# WM1302_915_USB_without_SX1262_SKY66420_v.net
KiCad netlist of a schematic drawn in EAGLE
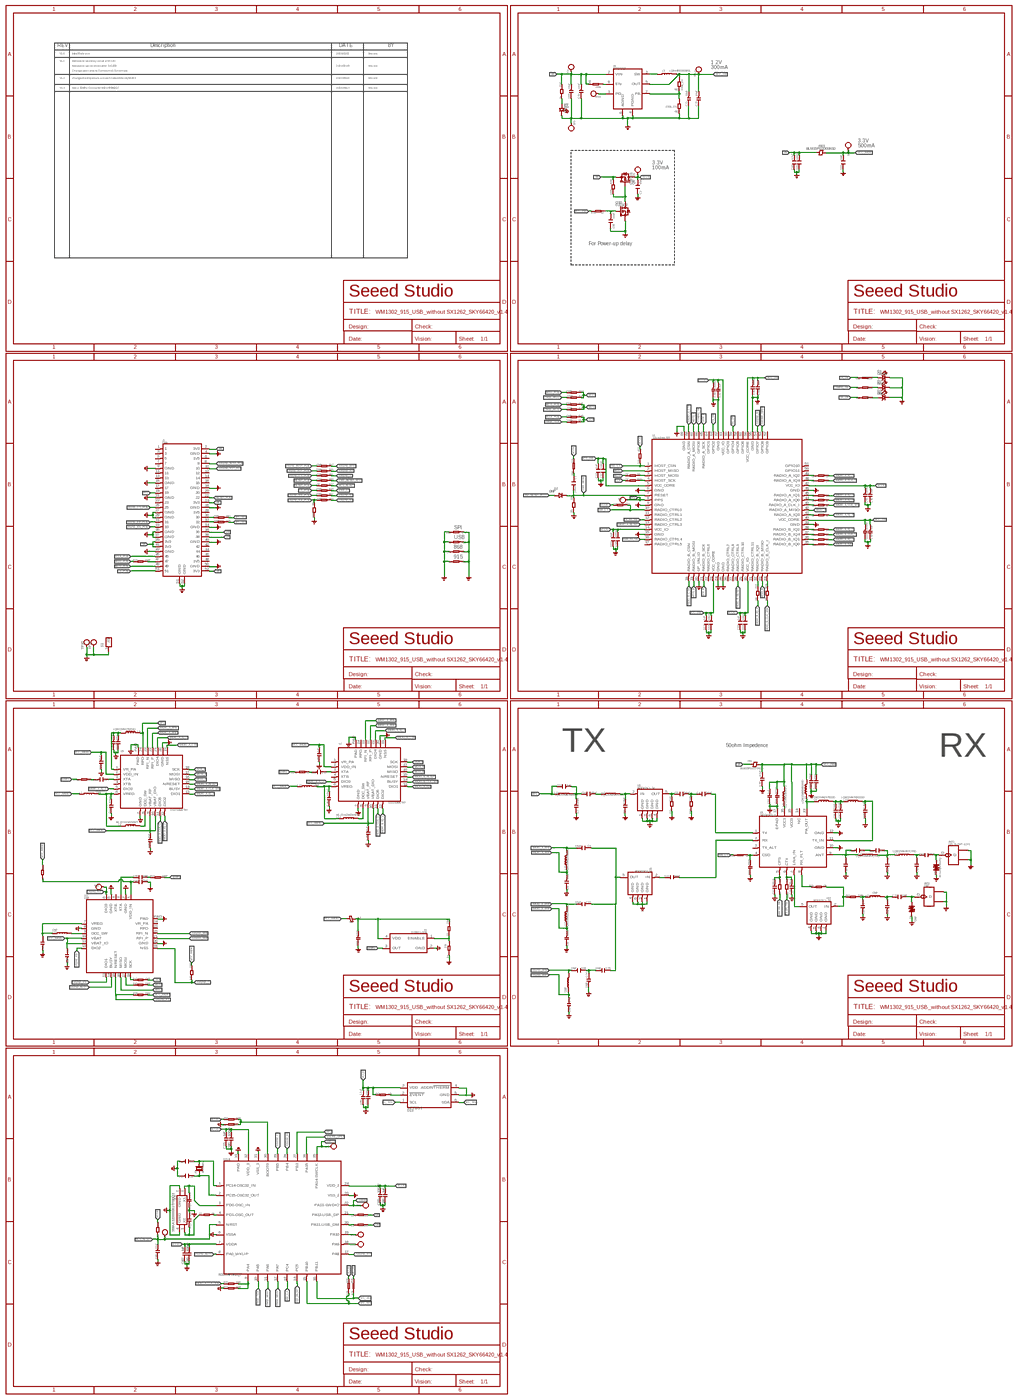
[diagram p0: schematic, sheet 1, overview]
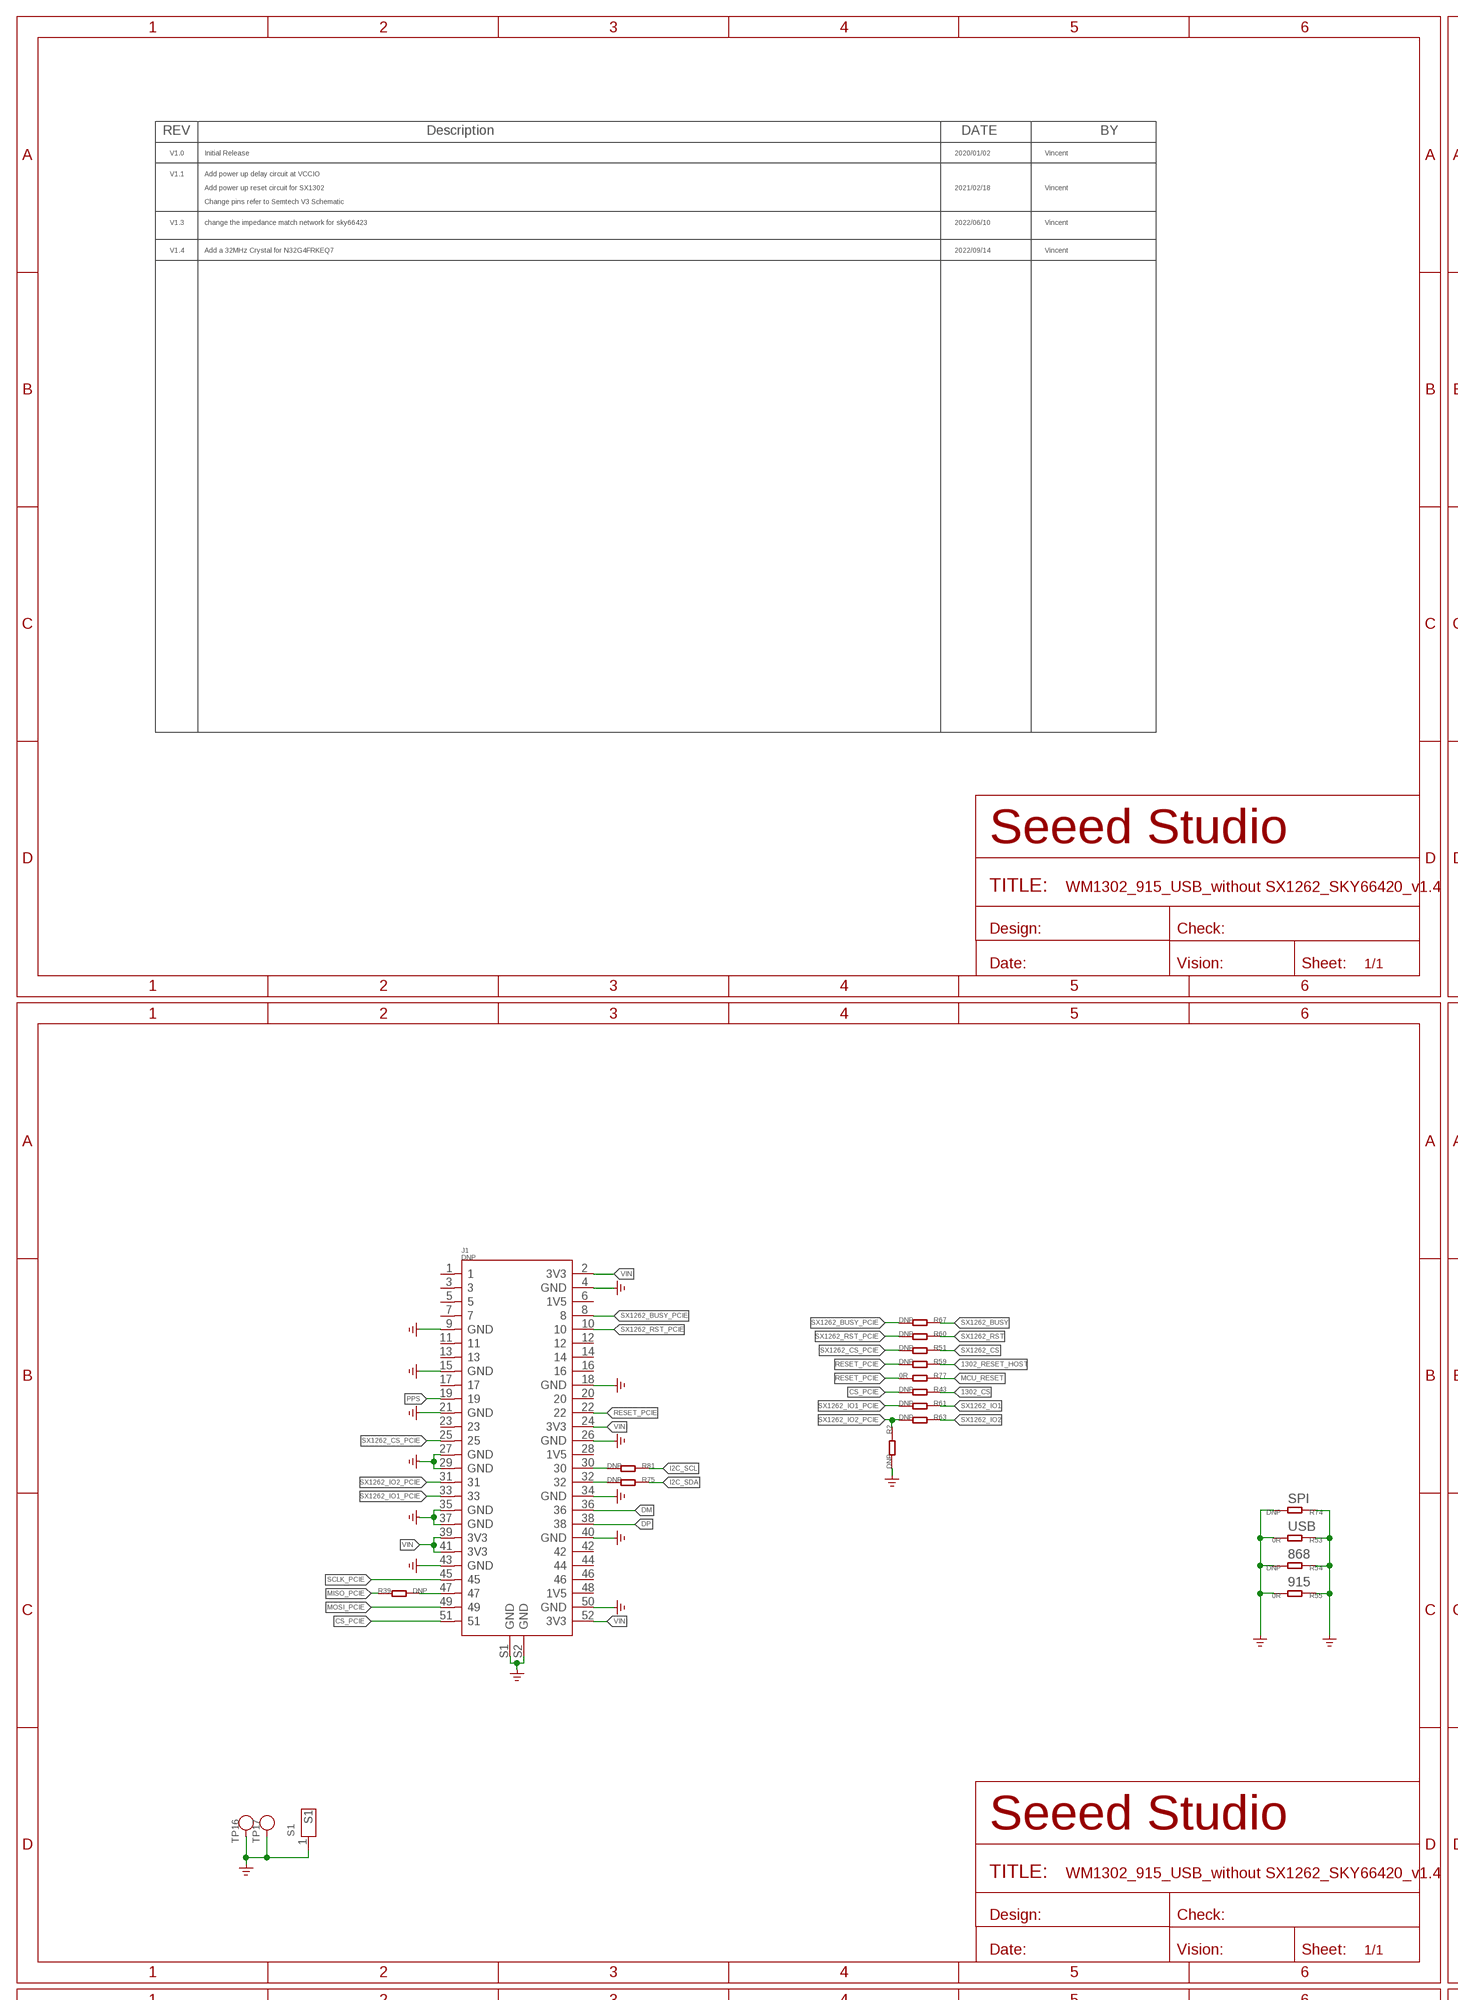
[diagram p1: schematic, sheet 1, part 1 of 4]
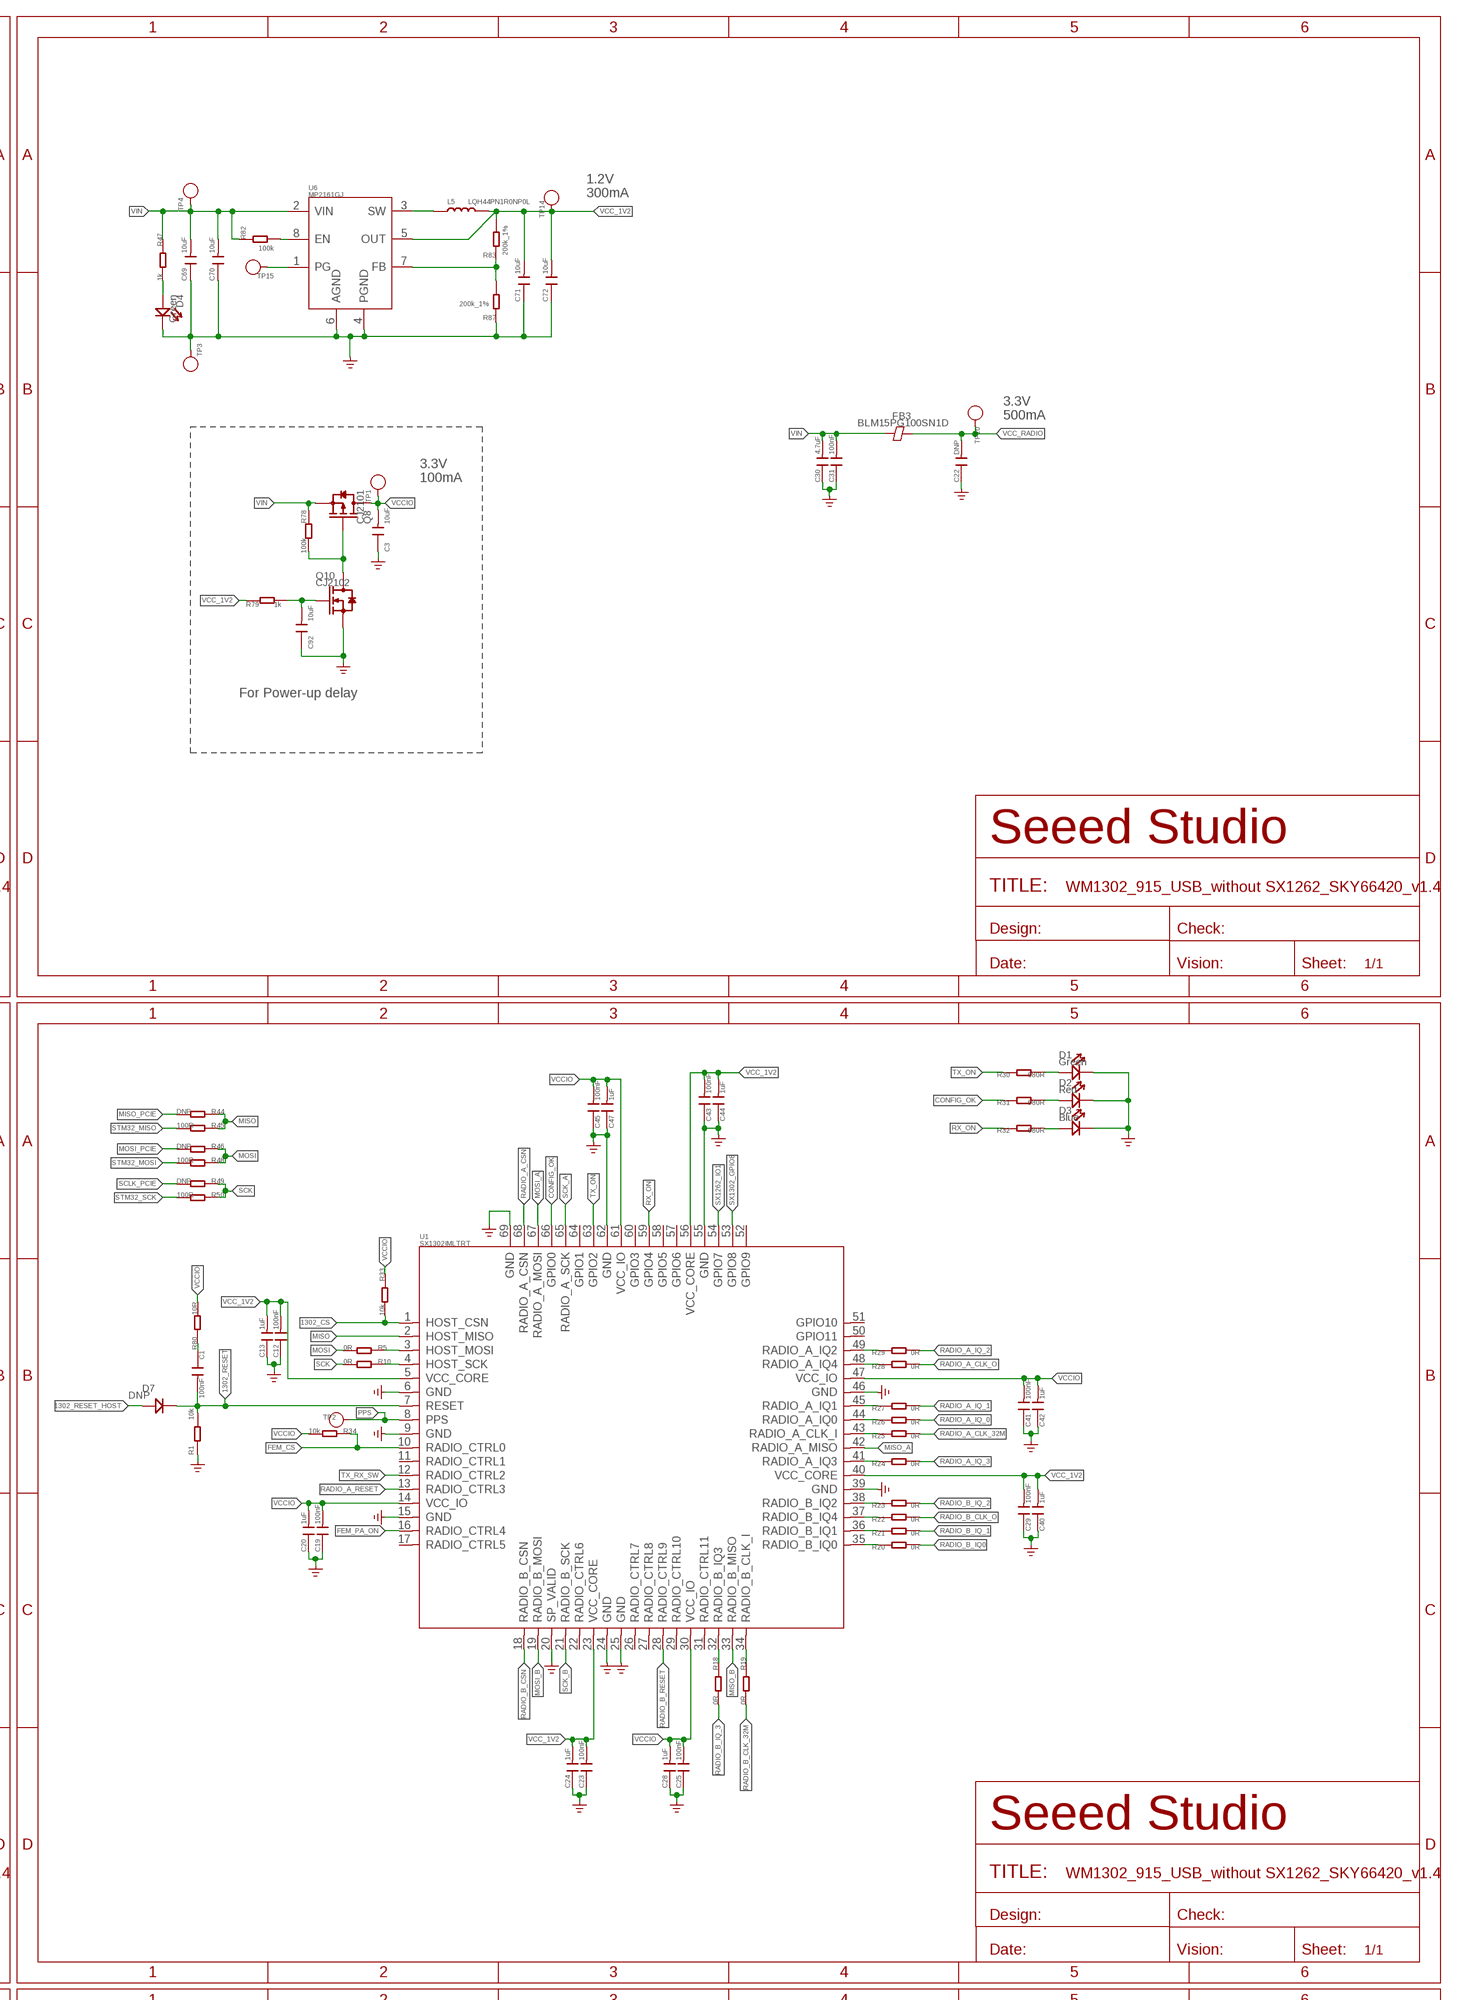
[diagram p2: schematic, sheet 1, part 2 of 4]
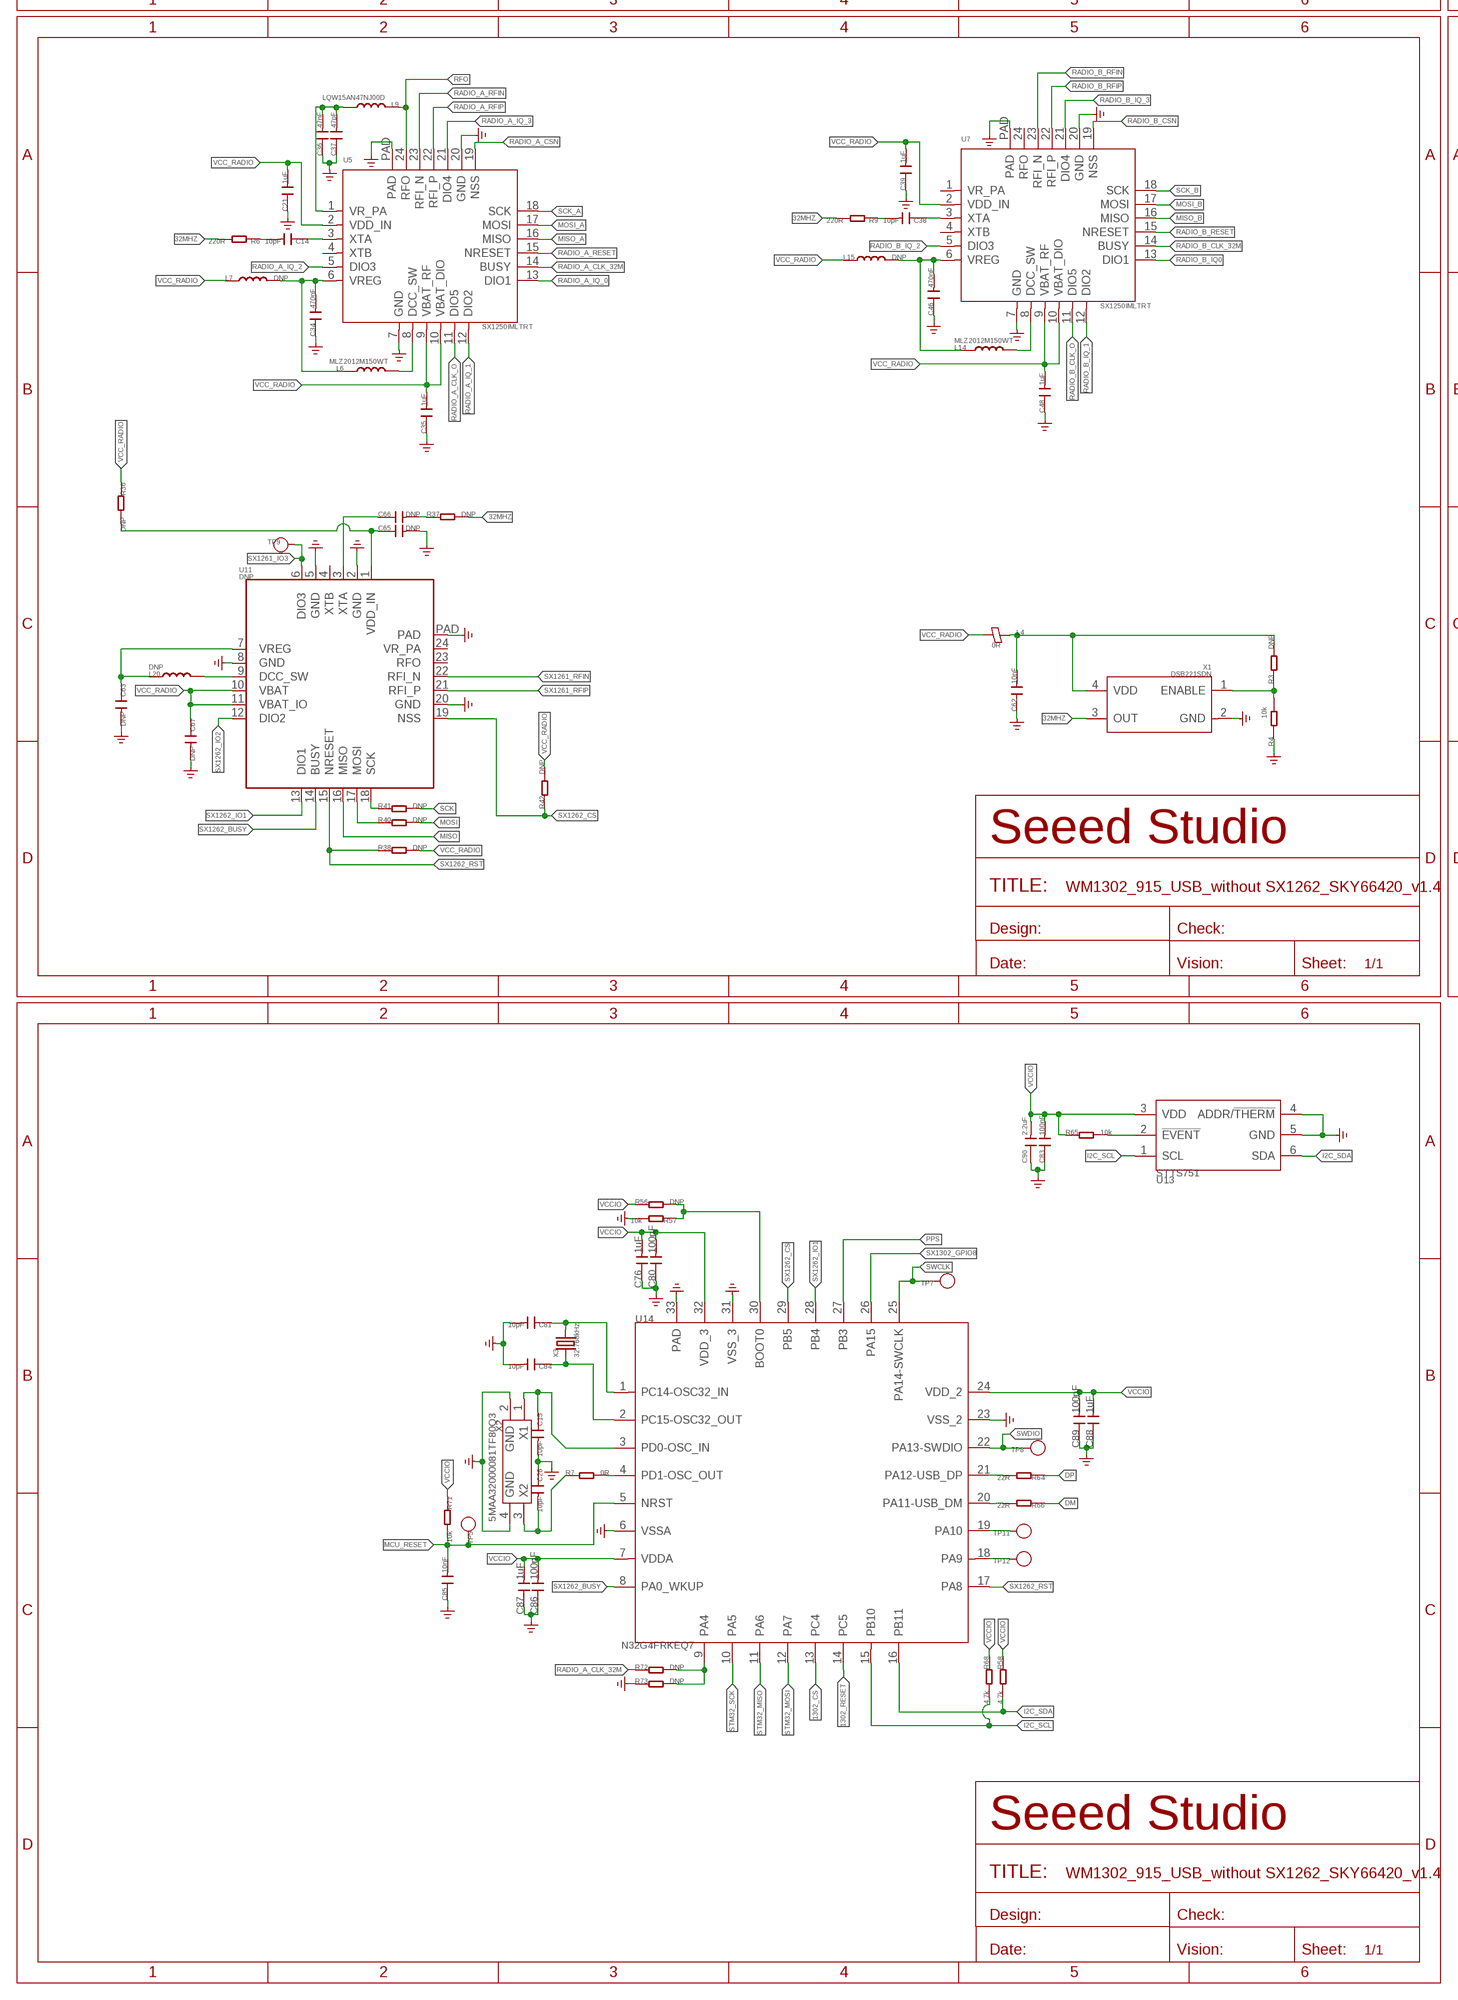
[diagram p3: schematic, sheet 1, part 3 of 4]
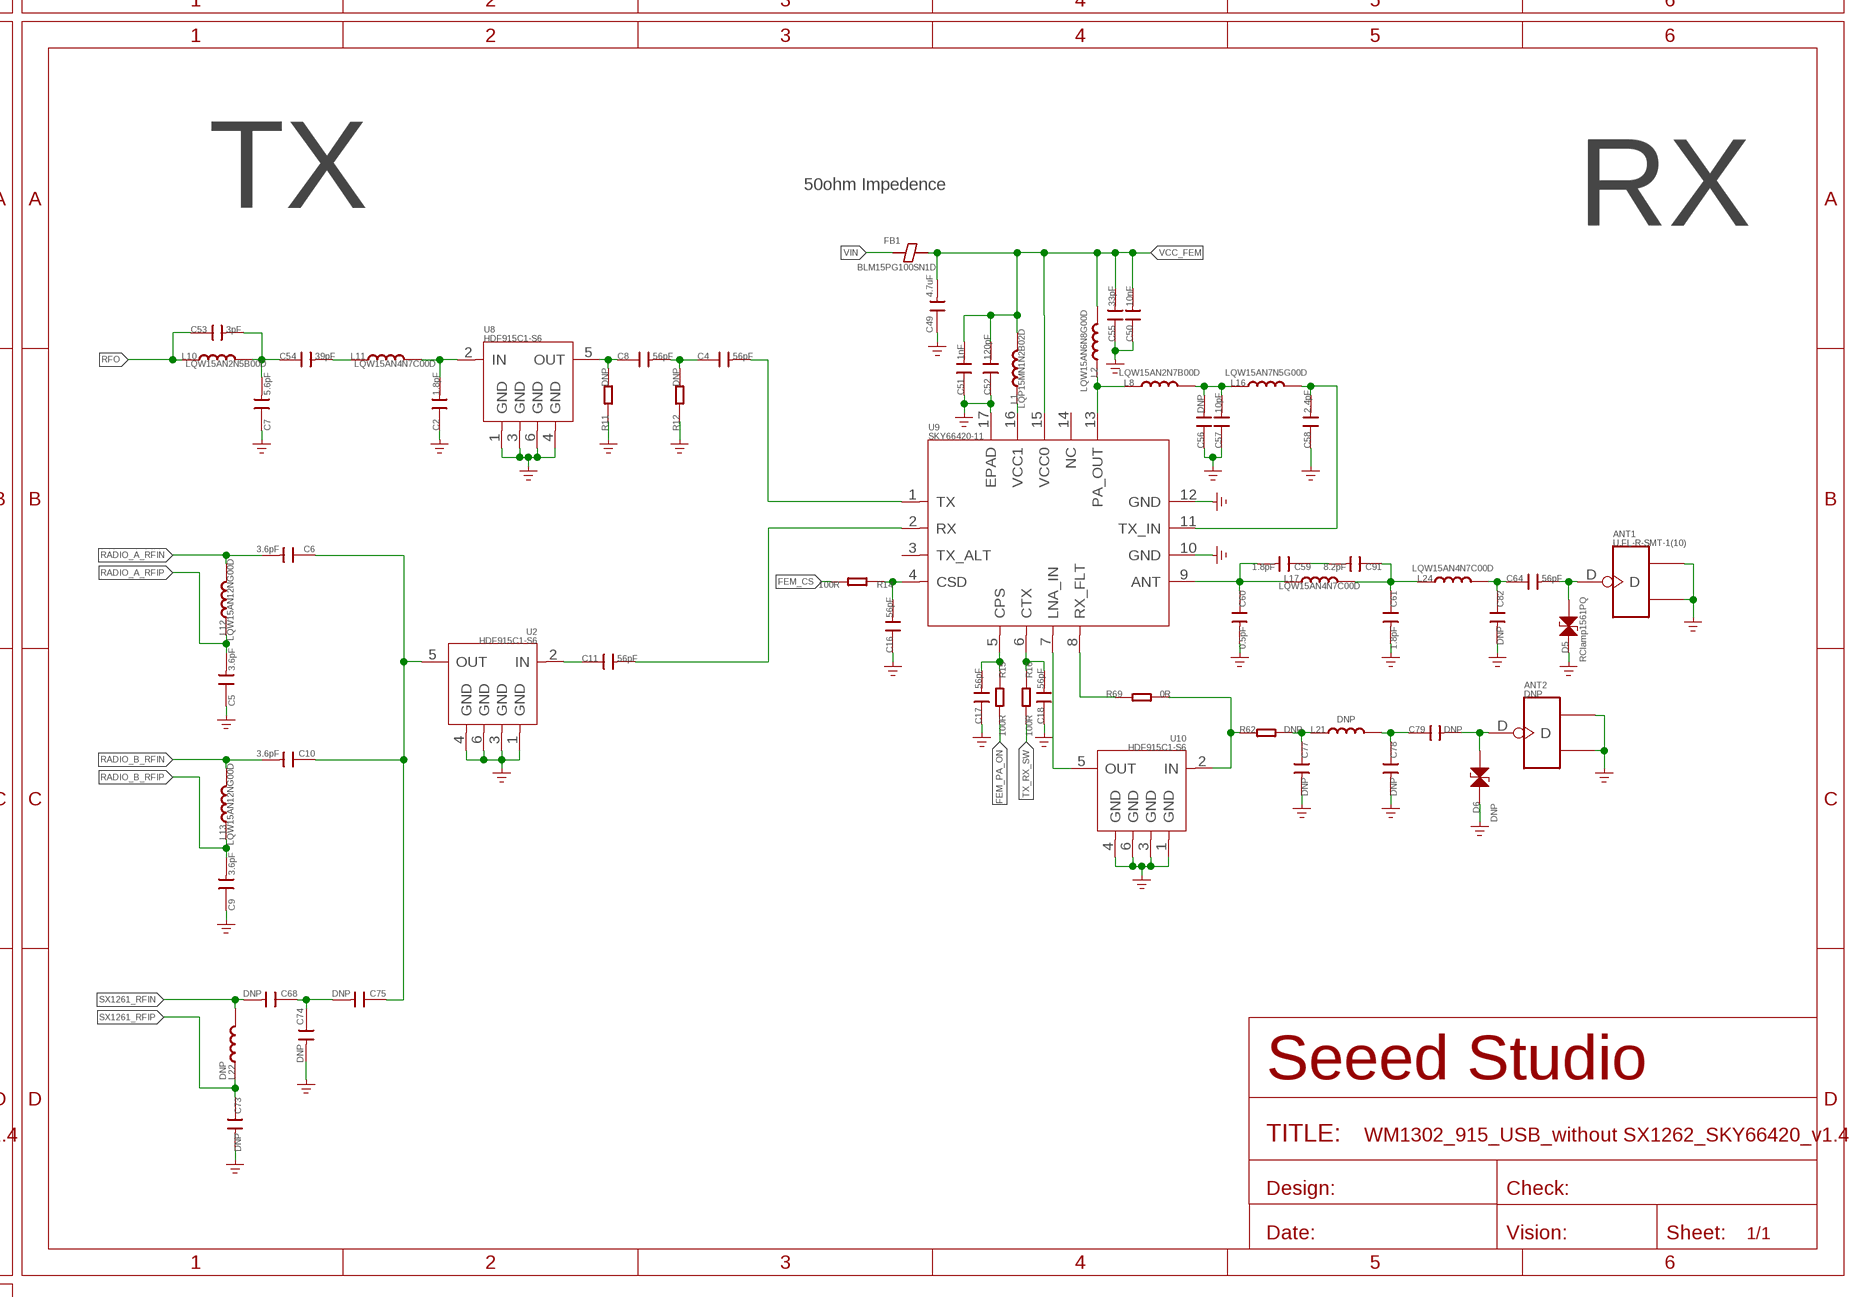
[diagram p4: schematic, sheet 1, part 4 of 4]

(export (version "E")
  (design (tool "Eeschema 10.0.6"))
  (components
    (comp (ref "ANT1")
      (value "U.FL-R-SMT-1(10)")
      (footprint "eagle-import:U-FL3P-SMD-2.6X2.6X1.0MM")
      (fields (field (name "SPICEPREFIX") "J"))
      (libsource (lib "eagle-import") (part "ANTENNA-U-FL-320110048"))
    )
    (comp (ref "ANT2")
      (value "DNP")
      (footprint "eagle-import:U-FL3P-SMD-2.6X2.6X1.0MM")
      (fields (field (name "SPICEPREFIX") "J"))
      (libsource (lib "eagle-import") (part "ANTENNA-U-FL-320110048"))
    )
    (comp (ref "C1")
      (value "100nF")
      (footprint "eagle-import:C0402")
      (libsource (lib "eagle-import") (part "C-0402"))
    )
    (comp (ref "C2")
      (value "1.8pF")
      (footprint "eagle-import:C0402")
      (libsource (lib "eagle-import") (part "C-0402"))
    )
    (comp (ref "C3")
      (value "10uF")
      (footprint "eagle-import:C0603")
      (libsource (lib "eagle-import") (part "C-0603"))
    )
    (comp (ref "C4")
      (value "56pF")
      (footprint "eagle-import:C0402")
      (libsource (lib "eagle-import") (part "C-0402"))
    )
    (comp (ref "C5")
      (value "3.6pF")
      (footprint "eagle-import:C0402")
      (libsource (lib "eagle-import") (part "C-0402"))
    )
    (comp (ref "C6")
      (value "3.6pF")
      (footprint "eagle-import:C0402")
      (libsource (lib "eagle-import") (part "C-0402"))
    )
    (comp (ref "C7")
      (value "5.6pF")
      (footprint "eagle-import:C0402")
      (libsource (lib "eagle-import") (part "C-0402"))
    )
    (comp (ref "C8")
      (value "56pF")
      (footprint "eagle-import:C0402")
      (libsource (lib "eagle-import") (part "C-0402"))
    )
    (comp (ref "C9")
      (value "3.6pF")
      (footprint "eagle-import:C0402")
      (libsource (lib "eagle-import") (part "C-0402"))
    )
    (comp (ref "C10")
      (value "3.6pF")
      (footprint "eagle-import:C0402")
      (libsource (lib "eagle-import") (part "C-0402"))
    )
    (comp (ref "C11")
      (value "56pF")
      (footprint "eagle-import:C0402")
      (libsource (lib "eagle-import") (part "C-0402"))
    )
    (comp (ref "C12")
      (value "100nF")
      (footprint "eagle-import:C0402")
      (libsource (lib "eagle-import") (part "C-0402"))
    )
    (comp (ref "C13")
      (value "1uF")
      (footprint "eagle-import:C0402")
      (libsource (lib "eagle-import") (part "C-0402"))
    )
    (comp (ref "C14")
      (value "10pF")
      (footprint "eagle-import:C0402")
      (libsource (lib "eagle-import") (part "C-0402"))
    )
    (comp (ref "C15")
      (value "10pF")
      (footprint "eagle-import:C0402")
      (libsource (lib "eagle-import") (part "C-0402"))
    )
    (comp (ref "C16")
      (value "56pF")
      (footprint "eagle-import:C0402")
      (libsource (lib "eagle-import") (part "C-0402"))
    )
    (comp (ref "C17")
      (value "56pF")
      (footprint "eagle-import:C0402")
      (libsource (lib "eagle-import") (part "C-0402"))
    )
    (comp (ref "C18")
      (value "56pF")
      (footprint "eagle-import:C0402")
      (libsource (lib "eagle-import") (part "C-0402"))
    )
    (comp (ref "C19")
      (value "100nF")
      (footprint "eagle-import:C0402")
      (libsource (lib "eagle-import") (part "C-0402"))
    )
    (comp (ref "C20")
      (value "1uF")
      (footprint "eagle-import:C0402")
      (libsource (lib "eagle-import") (part "C-0402"))
    )
    (comp (ref "C21")
      (value "1uF")
      (footprint "eagle-import:C0402")
      (libsource (lib "eagle-import") (part "C-0402"))
    )
    (comp (ref "C22")
      (value "DNP")
      (footprint "eagle-import:C0402")
      (libsource (lib "eagle-import") (part "C-0402"))
    )
    (comp (ref "C23")
      (value "100nF")
      (footprint "eagle-import:C0402")
      (libsource (lib "eagle-import") (part "C-0402"))
    )
    (comp (ref "C24")
      (value "1uF")
      (footprint "eagle-import:C0402")
      (libsource (lib "eagle-import") (part "C-0402"))
    )
    (comp (ref "C25")
      (value "100nF")
      (footprint "eagle-import:C0402")
      (libsource (lib "eagle-import") (part "C-0402"))
    )
    (comp (ref "C26")
      (value "10pF")
      (footprint "eagle-import:C0402")
      (libsource (lib "eagle-import") (part "C-0402"))
    )
    (comp (ref "C28")
      (value "1uF")
      (footprint "eagle-import:C0402")
      (libsource (lib "eagle-import") (part "C-0402"))
    )
    (comp (ref "C29")
      (value "100nF")
      (footprint "eagle-import:C0402")
      (libsource (lib "eagle-import") (part "C-0402"))
    )
    (comp (ref "C30")
      (value "4.7uF")
      (footprint "eagle-import:C0603")
      (libsource (lib "eagle-import") (part "C-0603"))
    )
    (comp (ref "C31")
      (value "100nF")
      (footprint "eagle-import:C0402")
      (libsource (lib "eagle-import") (part "C-0402"))
    )
    (comp (ref "C34")
      (value "470nF")
      (footprint "eagle-import:C0402")
      (libsource (lib "eagle-import") (part "C-0402"))
    )
    (comp (ref "C35")
      (value "1uF")
      (footprint "eagle-import:C0402")
      (libsource (lib "eagle-import") (part "C-0402"))
    )
    (comp (ref "C36")
      (value "47nF")
      (footprint "eagle-import:C0402")
      (libsource (lib "eagle-import") (part "C-0402"))
    )
    (comp (ref "C37")
      (value "47pF")
      (footprint "eagle-import:C0402")
      (libsource (lib "eagle-import") (part "C-0402"))
    )
    (comp (ref "C38")
      (value "10pF")
      (footprint "eagle-import:C0402")
      (libsource (lib "eagle-import") (part "C-0402"))
    )
    (comp (ref "C39")
      (value "1uF")
      (footprint "eagle-import:C0402")
      (libsource (lib "eagle-import") (part "C-0402"))
    )
    (comp (ref "C40")
      (value "1uF")
      (footprint "eagle-import:C0402")
      (libsource (lib "eagle-import") (part "C-0402"))
    )
    (comp (ref "C41")
      (value "100nF")
      (footprint "eagle-import:C0402")
      (libsource (lib "eagle-import") (part "C-0402"))
    )
    (comp (ref "C42")
      (value "1uF")
      (footprint "eagle-import:C0402")
      (libsource (lib "eagle-import") (part "C-0402"))
    )
    (comp (ref "C43")
      (value "100nF")
      (footprint "eagle-import:C0402")
      (libsource (lib "eagle-import") (part "C-0402"))
    )
    (comp (ref "C44")
      (value "1uF")
      (footprint "eagle-import:C0402")
      (libsource (lib "eagle-import") (part "C-0402"))
    )
    (comp (ref "C45")
      (value "100nF")
      (footprint "eagle-import:C0402")
      (libsource (lib "eagle-import") (part "C-0402"))
    )
    (comp (ref "C46")
      (value "470nF")
      (footprint "eagle-import:C0402")
      (libsource (lib "eagle-import") (part "C-0402"))
    )
    (comp (ref "C47")
      (value "1uF")
      (footprint "eagle-import:C0402")
      (libsource (lib "eagle-import") (part "C-0402"))
    )
    (comp (ref "C48")
      (value "1uF")
      (footprint "eagle-import:C0402")
      (libsource (lib "eagle-import") (part "C-0402"))
    )
    (comp (ref "C49")
      (value "4.7uF")
      (footprint "eagle-import:C0603")
      (libsource (lib "eagle-import") (part "C-0603"))
    )
    (comp (ref "C50")
      (value "10nF")
      (footprint "eagle-import:C0402")
      (libsource (lib "eagle-import") (part "C-0402"))
    )
    (comp (ref "C51")
      (value "1nF")
      (footprint "eagle-import:C0402")
      (libsource (lib "eagle-import") (part "C-0402"))
    )
    (comp (ref "C52")
      (value "120pF")
      (footprint "eagle-import:C0402")
      (libsource (lib "eagle-import") (part "C-0402"))
    )
    (comp (ref "C53")
      (value "3pF")
      (footprint "eagle-import:C0402")
      (libsource (lib "eagle-import") (part "C-0402"))
    )
    (comp (ref "C54")
      (value "39pF")
      (footprint "eagle-import:C0402")
      (libsource (lib "eagle-import") (part "C-0402"))
    )
    (comp (ref "C55")
      (value "33pF")
      (footprint "eagle-import:C0402")
      (fields (field (name "SPICEPREFIX") "C"))
      (libsource (lib "eagle-import") (part "C-0402"))
    )
    (comp (ref "C56")
      (value "DNP")
      (footprint "eagle-import:C0402")
      (libsource (lib "eagle-import") (part "C-0402"))
    )
    (comp (ref "C57")
      (value "10pF")
      (footprint "eagle-import:C0402")
      (libsource (lib "eagle-import") (part "C-0402"))
    )
    (comp (ref "C58")
      (value "2.4pF")
      (footprint "eagle-import:C0402")
      (libsource (lib "eagle-import") (part "C-0402"))
    )
    (comp (ref "C59")
      (value "1.8pF")
      (footprint "eagle-import:C0402")
      (libsource (lib "eagle-import") (part "C-0402"))
    )
    (comp (ref "C60")
      (value "0.5pF")
      (footprint "eagle-import:C0402")
      (libsource (lib "eagle-import") (part "C-0402"))
    )
    (comp (ref "C61")
      (value "1.8pF")
      (footprint "eagle-import:C0402")
      (libsource (lib "eagle-import") (part "C-0402"))
    )
    (comp (ref "C62")
      (value "10nF")
      (footprint "eagle-import:C0402")
      (libsource (lib "eagle-import") (part "C-0402"))
    )
    (comp (ref "C63")
      (value "DNP")
      (footprint "eagle-import:C0402")
      (libsource (lib "eagle-import") (part "C-0402"))
    )
    (comp (ref "C64")
      (value "56pF")
      (footprint "eagle-import:C0402")
      (libsource (lib "eagle-import") (part "C-0402"))
    )
    (comp (ref "C65")
      (value "DNP")
      (footprint "eagle-import:C0402")
      (libsource (lib "eagle-import") (part "C-0402"))
    )
    (comp (ref "C66")
      (value "DNP")
      (footprint "eagle-import:C0402")
      (libsource (lib "eagle-import") (part "C-0402"))
    )
    (comp (ref "C67")
      (value "DNP")
      (footprint "eagle-import:C0402")
      (libsource (lib "eagle-import") (part "C-0402"))
    )
    (comp (ref "C68")
      (value "DNP")
      (footprint "eagle-import:C0402")
      (libsource (lib "eagle-import") (part "C-0402"))
    )
    (comp (ref "C69")
      (value "10uF")
      (footprint "eagle-import:C0805")
      (libsource (lib "eagle-import") (part "CAP-0805"))
    )
    (comp (ref "C70")
      (value "10uF")
      (footprint "eagle-import:C0805")
      (libsource (lib "eagle-import") (part "CAP-0805"))
    )
    (comp (ref "C71")
      (value "10uF")
      (footprint "eagle-import:C0805")
      (libsource (lib "eagle-import") (part "CAP-0805"))
    )
    (comp (ref "C72")
      (value "10uF")
      (footprint "eagle-import:C0805")
      (libsource (lib "eagle-import") (part "CAP-0805"))
    )
    (comp (ref "C73")
      (value "DNP")
      (footprint "eagle-import:C0402")
      (libsource (lib "eagle-import") (part "C-0402"))
    )
    (comp (ref "C74")
      (value "DNP")
      (footprint "eagle-import:C0402")
      (libsource (lib "eagle-import") (part "C-0402"))
    )
    (comp (ref "C75")
      (value "DNP")
      (footprint "eagle-import:C0402")
      (libsource (lib "eagle-import") (part "C-0402"))
    )
    (comp (ref "C76")
      (value "1uF")
      (footprint "eagle-import:C0402")
      (libsource (lib "eagle-import") (part "C-0402"))
    )
    (comp (ref "C77")
      (value "DNP")
      (footprint "eagle-import:C0402")
      (libsource (lib "eagle-import") (part "C-0402"))
    )
    (comp (ref "C78")
      (value "DNP")
      (footprint "eagle-import:C0402")
      (libsource (lib "eagle-import") (part "C-0402"))
    )
    (comp (ref "C79")
      (value "DNP")
      (footprint "eagle-import:C0402")
      (libsource (lib "eagle-import") (part "C-0402"))
    )
    (comp (ref "C80")
      (value "100nF")
      (footprint "eagle-import:C0402")
      (libsource (lib "eagle-import") (part "C-0402"))
    )
    (comp (ref "C81")
      (value "10pF")
      (footprint "eagle-import:C0402")
      (libsource (lib "eagle-import") (part "C-0402"))
    )
    (comp (ref "C82")
      (value "DNP")
      (footprint "eagle-import:C0402")
      (libsource (lib "eagle-import") (part "C-0402"))
    )
    (comp (ref "C83")
      (value "100nF")
      (footprint "eagle-import:C0402")
      (libsource (lib "eagle-import") (part "C-0402"))
    )
    (comp (ref "C84")
      (value "10pF")
      (footprint "eagle-import:C0402")
      (libsource (lib "eagle-import") (part "C-0402"))
    )
    (comp (ref "C85")
      (value "10nF")
      (footprint "eagle-import:C0402")
      (libsource (lib "eagle-import") (part "C-0402"))
    )
    (comp (ref "C86")
      (value "100nF")
      (footprint "eagle-import:C0402")
      (libsource (lib "eagle-import") (part "C-0402"))
    )
    (comp (ref "C87")
      (value "1uF")
      (footprint "eagle-import:C0402")
      (libsource (lib "eagle-import") (part "C-0402"))
    )
    (comp (ref "C88")
      (value "1uF")
      (footprint "eagle-import:C0402")
      (libsource (lib "eagle-import") (part "C-0402"))
    )
    (comp (ref "C89")
      (value "100nF")
      (footprint "eagle-import:C0402")
      (libsource (lib "eagle-import") (part "C-0402"))
    )
    (comp (ref "C90")
      (value "2.2uF")
      (footprint "eagle-import:C0603")
      (libsource (lib "eagle-import") (part "C-0603"))
    )
    (comp (ref "C91")
      (value "8.2pF")
      (footprint "eagle-import:C0402")
      (libsource (lib "eagle-import") (part "C-0402"))
    )
    (comp (ref "C92")
      (value "10uF")
      (footprint "eagle-import:C0603")
      (libsource (lib "eagle-import") (part "C-0603"))
    )
    (comp (ref "D1")
      (value "Green")
      (footprint "eagle-import:LED-0402")
      (libsource (lib "eagle-import") (part "LED-0402"))
    )
    (comp (ref "D2")
      (value "Red")
      (footprint "eagle-import:LED-0402")
      (libsource (lib "eagle-import") (part "LED-0402"))
    )
    (comp (ref "D3")
      (value "Blue")
      (footprint "eagle-import:LED-0402")
      (libsource (lib "eagle-import") (part "LED-0402"))
    )
    (comp (ref "D4")
      (value "Green")
      (footprint "eagle-import:LED-0402")
      (libsource (lib "eagle-import") (part "LED-0402"))
    )
    (comp (ref "D5")
      (value "RClamp1561PQ")
      (footprint "eagle-import:ESD-0402")
      (fields (field (name "SPICEPREFIX") "D"))
      (libsource (lib "eagle-import") (part "D-ESD-2P-DOUBLE-0402"))
    )
    (comp (ref "D6")
      (value "DNP")
      (footprint "eagle-import:ESD-0402")
      (libsource (lib "eagle-import") (part "D-ESD-2P-DOUBLE-0402"))
    )
    (comp (ref "D7")
      (value "DNP")
      (footprint "eagle-import:SOD-523")
      (libsource (lib "eagle-import") (part "DIODE'0603'"))
    )
    (comp (ref "FB1")
      (value "BLM15PG100SN1D")
      (footprint "eagle-import:F0402")
      (libsource (lib "eagle-import") (part "FERRITE-BEAD-0402"))
    )
    (comp (ref "FB3")
      (value "BLM15PG100SN1D")
      (footprint "eagle-import:F0402")
      (libsource (lib "eagle-import") (part "FERRITE-BEAD-0402"))
    )
    (comp (ref "J1")
      (value "DNP")
      (footprint "eagle-import:PCIE52P-0.8-50.95X30MM")
      (libsource (lib "eagle-import") (part "MOUDLE-FULL-MINI-PCIE"))
    )
    (comp (ref "L1")
      (value "LQP15MN1N2B02D")
      (footprint "eagle-import:L0402")
      (libsource (lib "eagle-import") (part "L-0402"))
    )
    (comp (ref "L2")
      (value "LQW15AN6N8G00D")
      (footprint "eagle-import:L0402")
      (libsource (lib "eagle-import") (part "L-0402"))
    )
    (comp (ref "L4")
      (value "0R")
      (footprint "eagle-import:F0603")
      (libsource (lib "eagle-import") (part "FERRITE-BEAD-0603"))
    )
    (comp (ref "L5")
      (value "LQH44PN1R0NP0L")
      (footprint "eagle-import:L4.4X3.0MM")
      (libsource (lib "eagle-import") (part "INDUCTOR-4430"))
    )
    (comp (ref "L6")
      (value "MLZ2012M150WT")
      (footprint "eagle-import:L202012")
      (libsource (lib "eagle-import") (part "INDUCTOR-SPH202012"))
    )
    (comp (ref "L7")
      (value "DNP")
      (footprint "eagle-import:L0402")
      (libsource (lib "eagle-import") (part "L-0402"))
    )
    (comp (ref "L8")
      (value "LQW15AN2N7B00D")
      (footprint "eagle-import:L0402")
      (libsource (lib "eagle-import") (part "L-0402"))
    )
    (comp (ref "L9")
      (value "LQW15AN47NJ00D")
      (footprint "eagle-import:L0402")
      (libsource (lib "eagle-import") (part "L-0402"))
    )
    (comp (ref "L10")
      (value "LQW15AN2N5B00D")
      (footprint "eagle-import:L0402")
      (libsource (lib "eagle-import") (part "L-0402"))
    )
    (comp (ref "L11")
      (value "LQW15AN4N7C00D")
      (footprint "eagle-import:L0402")
      (libsource (lib "eagle-import") (part "L-0402"))
    )
    (comp (ref "L12")
      (value "LQW15AN12NG00D")
      (footprint "eagle-import:L0402")
      (libsource (lib "eagle-import") (part "L-0402"))
    )
    (comp (ref "L13")
      (value "LQW15AN12NG00D")
      (footprint "eagle-import:L0402")
      (libsource (lib "eagle-import") (part "L-0402"))
    )
    (comp (ref "L14")
      (value "MLZ2012M150WT")
      (footprint "eagle-import:L202012")
      (libsource (lib "eagle-import") (part "INDUCTOR-SPH202012"))
    )
    (comp (ref "L15")
      (value "DNP")
      (footprint "eagle-import:L0402")
      (libsource (lib "eagle-import") (part "L-0402"))
    )
    (comp (ref "L16")
      (value "LQW15AN7N5G00D")
      (footprint "eagle-import:L0402")
      (libsource (lib "eagle-import") (part "L-0402"))
    )
    (comp (ref "L17")
      (value "LQW15AN4N7C00D")
      (footprint "eagle-import:L0402")
      (libsource (lib "eagle-import") (part "L-0402"))
    )
    (comp (ref "L20")
      (value "DNP")
      (footprint "eagle-import:L202012")
      (libsource (lib "eagle-import") (part "INDUCTOR-SPH202012"))
    )
    (comp (ref "L21")
      (value "DNP")
      (footprint "eagle-import:L0402")
      (libsource (lib "eagle-import") (part "L-0402"))
    )
    (comp (ref "L22")
      (value "DNP")
      (footprint "eagle-import:L0402")
      (libsource (lib "eagle-import") (part "L-0402"))
    )
    (comp (ref "L24")
      (value "LQW15AN4N7C00D")
      (footprint "eagle-import:L0402")
      (libsource (lib "eagle-import") (part "L-0402"))
    )
    (comp (ref "Q8")
      (value "CJ2101")
      (footprint "eagle-import:SOT-323")
      (libsource (lib "eagle-import") (part "MOSFET-P-SOT323"))
    )
    (comp (ref "Q10")
      (value "CJ2102")
      (footprint "eagle-import:SOT-323")
      (libsource (lib "eagle-import") (part "MOSFET-N-SI1304BDL"))
    )
    (comp (ref "R1")
      (value "10k")
      (footprint "eagle-import:R0402")
      (libsource (lib "eagle-import") (part "R-0402"))
    )
    (comp (ref "R2")
      (value "DNP")
      (footprint "eagle-import:R0402")
      (libsource (lib "eagle-import") (part "R-0402"))
    )
    (comp (ref "R3")
      (value "DNP")
      (footprint "eagle-import:R0402")
      (libsource (lib "eagle-import") (part "R-0402"))
    )
    (comp (ref "R4")
      (value "10k")
      (footprint "eagle-import:R0402")
      (libsource (lib "eagle-import") (part "R-0402"))
    )
    (comp (ref "R5")
      (value "0R")
      (footprint "eagle-import:R0402")
      (libsource (lib "eagle-import") (part "R-0402"))
    )
    (comp (ref "R6")
      (value "220R")
      (footprint "eagle-import:R0402")
      (libsource (lib "eagle-import") (part "R-0402"))
    )
    (comp (ref "R7")
      (value "0R")
      (footprint "eagle-import:R0402")
      (libsource (lib "eagle-import") (part "R-0402"))
    )
    (comp (ref "R9")
      (value "220R")
      (footprint "eagle-import:R0402")
      (libsource (lib "eagle-import") (part "R-0402"))
    )
    (comp (ref "R10")
      (value "0R")
      (footprint "eagle-import:R0402")
      (libsource (lib "eagle-import") (part "R-0402"))
    )
    (comp (ref "R11")
      (value "DNP")
      (footprint "eagle-import:R0402")
      (libsource (lib "eagle-import") (part "R-0402"))
    )
    (comp (ref "R12")
      (value "DNP")
      (footprint "eagle-import:R0402")
      (libsource (lib "eagle-import") (part "R-0402"))
    )
    (comp (ref "R14")
      (value "100R")
      (footprint "eagle-import:R0402")
      (libsource (lib "eagle-import") (part "R-0402"))
    )
    (comp (ref "R15")
      (value "100R")
      (footprint "eagle-import:R0402")
      (libsource (lib "eagle-import") (part "R-0402"))
    )
    (comp (ref "R16")
      (value "100R")
      (footprint "eagle-import:R0402")
      (libsource (lib "eagle-import") (part "R-0402"))
    )
    (comp (ref "R18")
      (value "0R")
      (footprint "eagle-import:R0402")
      (libsource (lib "eagle-import") (part "R-0402"))
    )
    (comp (ref "R19")
      (value "0R")
      (footprint "eagle-import:R0402")
      (libsource (lib "eagle-import") (part "R-0402"))
    )
    (comp (ref "R20")
      (value "0R")
      (footprint "eagle-import:R0402")
      (libsource (lib "eagle-import") (part "R-0402"))
    )
    (comp (ref "R21")
      (value "0R")
      (footprint "eagle-import:R0402")
      (libsource (lib "eagle-import") (part "R-0402"))
    )
    (comp (ref "R22")
      (value "0R")
      (footprint "eagle-import:R0402")
      (libsource (lib "eagle-import") (part "R-0402"))
    )
    (comp (ref "R23")
      (value "0R")
      (footprint "eagle-import:R0402")
      (libsource (lib "eagle-import") (part "R-0402"))
    )
    (comp (ref "R24")
      (value "0R")
      (footprint "eagle-import:R0402")
      (libsource (lib "eagle-import") (part "R-0402"))
    )
    (comp (ref "R25")
      (value "0R")
      (footprint "eagle-import:R0402")
      (libsource (lib "eagle-import") (part "R-0402"))
    )
    (comp (ref "R26")
      (value "0R")
      (footprint "eagle-import:R0402")
      (libsource (lib "eagle-import") (part "R-0402"))
    )
    (comp (ref "R27")
      (value "0R")
      (footprint "eagle-import:R0402")
      (libsource (lib "eagle-import") (part "R-0402"))
    )
    (comp (ref "R28")
      (value "0R")
      (footprint "eagle-import:R0402")
      (libsource (lib "eagle-import") (part "R-0402"))
    )
    (comp (ref "R29")
      (value "0R")
      (footprint "eagle-import:R0402")
      (libsource (lib "eagle-import") (part "R-0402"))
    )
    (comp (ref "R30")
      (value "680R")
      (footprint "eagle-import:R0402")
      (libsource (lib "eagle-import") (part "R-0402"))
    )
    (comp (ref "R31")
      (value "680R")
      (footprint "eagle-import:R0402")
      (libsource (lib "eagle-import") (part "R-0402"))
    )
    (comp (ref "R32")
      (value "680R")
      (footprint "eagle-import:R0402")
      (libsource (lib "eagle-import") (part "R-0402"))
    )
    (comp (ref "R33")
      (value "10k")
      (footprint "eagle-import:R0402")
      (libsource (lib "eagle-import") (part "R-0402"))
    )
    (comp (ref "R34")
      (value "10k")
      (footprint "eagle-import:R0402")
      (libsource (lib "eagle-import") (part "R-0402"))
    )
    (comp (ref "R36")
      (value "DNP")
      (footprint "eagle-import:R0402")
      (libsource (lib "eagle-import") (part "R-0402"))
    )
    (comp (ref "R37")
      (value "DNP")
      (footprint "eagle-import:R0402")
      (libsource (lib "eagle-import") (part "R-0402"))
    )
    (comp (ref "R38")
      (value "DNP")
      (footprint "eagle-import:R0402")
      (libsource (lib "eagle-import") (part "R-0402"))
    )
    (comp (ref "R39")
      (value "DNP")
      (footprint "eagle-import:R0402")
      (libsource (lib "eagle-import") (part "R-0402"))
    )
    (comp (ref "R40")
      (value "DNP")
      (footprint "eagle-import:R0402")
      (libsource (lib "eagle-import") (part "R-0402"))
    )
    (comp (ref "R41")
      (value "DNP")
      (footprint "eagle-import:R0402")
      (libsource (lib "eagle-import") (part "R-0402"))
    )
    (comp (ref "R42")
      (value "DNP")
      (footprint "eagle-import:R0402")
      (libsource (lib "eagle-import") (part "R-0402"))
    )
    (comp (ref "R43")
      (value "DNP")
      (footprint "eagle-import:R0402")
      (libsource (lib "eagle-import") (part "R-0402"))
    )
    (comp (ref "R44")
      (value "DNP")
      (footprint "eagle-import:R0402")
      (libsource (lib "eagle-import") (part "R-0402"))
    )
    (comp (ref "R45")
      (value "100R")
      (footprint "eagle-import:R0402")
      (libsource (lib "eagle-import") (part "R-0402"))
    )
    (comp (ref "R46")
      (value "DNP")
      (footprint "eagle-import:R0402")
      (libsource (lib "eagle-import") (part "R-0402"))
    )
    (comp (ref "R47")
      (value "1k")
      (footprint "eagle-import:R0402")
      (libsource (lib "eagle-import") (part "R-0402"))
    )
    (comp (ref "R48")
      (value "100R")
      (footprint "eagle-import:R0402")
      (libsource (lib "eagle-import") (part "R-0402"))
    )
    (comp (ref "R49")
      (value "DNP")
      (footprint "eagle-import:R0402")
      (libsource (lib "eagle-import") (part "R-0402"))
    )
    (comp (ref "R50")
      (value "100R")
      (footprint "eagle-import:R0402")
      (libsource (lib "eagle-import") (part "R-0402"))
    )
    (comp (ref "R51")
      (value "DNP")
      (footprint "eagle-import:R0402")
      (libsource (lib "eagle-import") (part "R-0402"))
    )
    (comp (ref "R53")
      (value "0R")
      (footprint "eagle-import:R0402")
      (libsource (lib "eagle-import") (part "R-0402"))
    )
    (comp (ref "R54")
      (value "DNP")
      (footprint "eagle-import:R0402")
      (libsource (lib "eagle-import") (part "R-0402"))
    )
    (comp (ref "R55")
      (value "0R")
      (footprint "eagle-import:R0402")
      (libsource (lib "eagle-import") (part "R-0402"))
    )
    (comp (ref "R56")
      (value "DNP")
      (footprint "eagle-import:R0402")
      (libsource (lib "eagle-import") (part "R-0402"))
    )
    (comp (ref "R57")
      (value "10k")
      (footprint "eagle-import:R0402")
      (libsource (lib "eagle-import") (part "R-0402"))
    )
    (comp (ref "R58")
      (value "4.7k")
      (footprint "eagle-import:R0402")
      (libsource (lib "eagle-import") (part "R-0402"))
    )
    (comp (ref "R59")
      (value "DNP")
      (footprint "eagle-import:R0402")
      (libsource (lib "eagle-import") (part "R-0402"))
    )
    (comp (ref "R60")
      (value "DNP")
      (footprint "eagle-import:R0402")
      (libsource (lib "eagle-import") (part "R-0402"))
    )
    (comp (ref "R61")
      (value "DNP")
      (footprint "eagle-import:R0402")
      (libsource (lib "eagle-import") (part "R-0402"))
    )
    (comp (ref "R62")
      (value "DNP")
      (footprint "eagle-import:R0402")
      (libsource (lib "eagle-import") (part "R-0402"))
    )
    (comp (ref "R63")
      (value "DNP")
      (footprint "eagle-import:R0402")
      (libsource (lib "eagle-import") (part "R-0402"))
    )
    (comp (ref "R64")
      (value "22R")
      (footprint "eagle-import:R0402")
      (libsource (lib "eagle-import") (part "R-0402"))
    )
    (comp (ref "R65")
      (value "10k")
      (footprint "eagle-import:R0402")
      (libsource (lib "eagle-import") (part "R-0402"))
    )
    (comp (ref "R66")
      (value "22R")
      (footprint "eagle-import:R0402")
      (libsource (lib "eagle-import") (part "R-0402"))
    )
    (comp (ref "R67")
      (value "DNP")
      (footprint "eagle-import:R0402")
      (libsource (lib "eagle-import") (part "R-0402"))
    )
    (comp (ref "R68")
      (value "4.7k")
      (footprint "eagle-import:R0402")
      (libsource (lib "eagle-import") (part "R-0402"))
    )
    (comp (ref "R69")
      (value "0R")
      (footprint "eagle-import:R0402")
      (libsource (lib "eagle-import") (part "R-0402"))
    )
    (comp (ref "R71")
      (value "10k")
      (footprint "eagle-import:R0402")
      (libsource (lib "eagle-import") (part "R-0402"))
    )
    (comp (ref "R72")
      (value "DNP")
      (footprint "eagle-import:R0402")
      (libsource (lib "eagle-import") (part "R-0402"))
    )
    (comp (ref "R73")
      (value "DNP")
      (footprint "eagle-import:R0402")
      (libsource (lib "eagle-import") (part "R-0402"))
    )
    (comp (ref "R74")
      (value "DNP")
      (footprint "eagle-import:R0402")
      (libsource (lib "eagle-import") (part "R-0402"))
    )
    (comp (ref "R75")
      (value "DNP")
      (footprint "eagle-import:R0402")
      (libsource (lib "eagle-import") (part "R-0402"))
    )
    (comp (ref "R77")
      (value "0R")
      (footprint "eagle-import:R0402")
      (libsource (lib "eagle-import") (part "R-0402"))
    )
    (comp (ref "R78")
      (value "100k")
      (footprint "eagle-import:R0402")
      (libsource (lib "eagle-import") (part "R-0402"))
    )
    (comp (ref "R79")
      (value "1k")
      (footprint "eagle-import:R0402")
      (libsource (lib "eagle-import") (part "R-0402"))
    )
    (comp (ref "R80")
      (value "10R")
      (footprint "eagle-import:R0402")
      (libsource (lib "eagle-import") (part "R-0402"))
    )
    (comp (ref "R81")
      (value "DNP")
      (footprint "eagle-import:R0402")
      (libsource (lib "eagle-import") (part "R-0402"))
    )
    (comp (ref "R82")
      (value "100k")
      (footprint "eagle-import:R0402")
      (libsource (lib "eagle-import") (part "R-0402"))
    )
    (comp (ref "R83")
      (value "200k_1%")
      (footprint "eagle-import:R0402")
      (libsource (lib "eagle-import") (part "R-0402"))
    )
    (comp (ref "R87")
      (value "200k_1%")
      (footprint "eagle-import:R0402")
      (libsource (lib "eagle-import") (part "R-0402"))
    )
    (comp (ref "S1")
      (value "SHIELD_CLIP-1302")
      (footprint "eagle-import:SHIELD_1302")
      (libsource (lib "eagle-import") (part "SHIELD_CLIP-1302"))
    )
    (comp (ref "TP1")
      (value "TEST-POINT-35")
      (footprint "eagle-import:TP_3535")
      (libsource (lib "eagle-import") (part "TEST-POINT-35"))
    )
    (comp (ref "TP2")
      (value "TEST-POINT-35")
      (footprint "eagle-import:TP_3535")
      (libsource (lib "eagle-import") (part "TEST-POINT-35"))
    )
    (comp (ref "TP3")
      (value "TEST-POINT-35")
      (footprint "eagle-import:TP_3535")
      (libsource (lib "eagle-import") (part "TEST-POINT-35"))
    )
    (comp (ref "TP4")
      (value "TEST-POINT-35")
      (footprint "eagle-import:TP_3535")
      (libsource (lib "eagle-import") (part "TEST-POINT-35"))
    )
    (comp (ref "TP5")
      (value "TEST-POINT-35")
      (footprint "eagle-import:TP_3535")
      (libsource (lib "eagle-import") (part "TEST-POINT-35"))
    )
    (comp (ref "TP7")
      (value "TEST-POINT-35")
      (footprint "eagle-import:TP_3535")
      (libsource (lib "eagle-import") (part "TEST-POINT-35"))
    )
    (comp (ref "TP8")
      (value "TEST-POINT-35")
      (footprint "eagle-import:TP_3535")
      (libsource (lib "eagle-import") (part "TEST-POINT-35"))
    )
    (comp (ref "TP9")
      (value "TEST-POINT-35")
      (footprint "eagle-import:TP_3535")
      (libsource (lib "eagle-import") (part "TEST-POINT-35"))
    )
    (comp (ref "TP10")
      (value "TEST-POINT-35")
      (footprint "eagle-import:TP_3535")
      (libsource (lib "eagle-import") (part "TEST-POINT-35"))
    )
    (comp (ref "TP11")
      (value "TEST-POINT-35")
      (footprint "eagle-import:TP_3535")
      (libsource (lib "eagle-import") (part "TEST-POINT-35"))
    )
    (comp (ref "TP12")
      (value "TEST-POINT-35")
      (footprint "eagle-import:TP_3535")
      (libsource (lib "eagle-import") (part "TEST-POINT-35"))
    )
    (comp (ref "TP14")
      (value "TEST-POINT-35")
      (footprint "eagle-import:TP_3535")
      (libsource (lib "eagle-import") (part "TEST-POINT-35"))
    )
    (comp (ref "TP15")
      (value "TEST-POINT'4545'")
      (footprint "eagle-import:TP-D45MIL")
      (fields (field (name "PARTNO") "DNP"))
      (libsource (lib "eagle-import") (part "TEST-POINT'4545'"))
    )
    (comp (ref "TP16")
      (value "TEST-POINT-1.9X0.3MM")
      (footprint "eagle-import:TEST-1.9X0.3MM")
      (libsource (lib "eagle-import") (part "TEST-POINT-1.9X0.3MM"))
    )
    (comp (ref "TP17")
      (value "TEST-POINT-1.9X0.3MM")
      (footprint "eagle-import:TEST-1.9X0.3MM")
      (libsource (lib "eagle-import") (part "TEST-POINT-1.9X0.3MM"))
    )
    (comp (ref "U1")
      (value "SX1302IMLTRT")
      (footprint "eagle-import:QFN68-0.35-7X7X0.75MM")
      (libsource (lib "eagle-import") (part "TRANSCEIVER-SX1302"))
    )
    (comp (ref "U2")
      (value "HDF915C1-S6")
      (footprint "eagle-import:FILTER6P-1.1-3X3X1.3MM")
      (libsource (lib "eagle-import") (part "FILTER-B39871B3717U410"))
    )
    (comp (ref "U5")
      (value "SX1250IMLTRT")
      (footprint "eagle-import:QFN24G-0.5-4X4MM")
      (libsource (lib "eagle-import") (part "RF-SX1250"))
    )
    (comp (ref "U6")
      (value "MP2161GJ")
      (footprint "eagle-import:TSOT23-8")
      (libsource (lib "eagle-import") (part "PMIC-MP2161'GJ'"))
    )
    (comp (ref "U7")
      (value "SX1250IMLTRT")
      (footprint "eagle-import:QFN24G-0.5-4X4MM")
      (libsource (lib "eagle-import") (part "RF-SX1250"))
    )
    (comp (ref "U8")
      (value "HDF915C1-S6")
      (footprint "eagle-import:FILTER6P-1.1-3X3X1.3MM")
      (libsource (lib "eagle-import") (part "FILTER-B39871B3717U410"))
    )
    (comp (ref "U9")
      (value "SKY66420-11")
      (footprint "eagle-import:MODULE16P-0.5-3X3X0.75MM")
      (libsource (lib "eagle-import") (part "MODULE-RF-SKY66420-11"))
    )
    (comp (ref "U10")
      (value "HDF915C1-S6")
      (footprint "eagle-import:FILTER6P-1.1-3X3X1.3MM")
      (libsource (lib "eagle-import") (part "FILTER-B39871B3717U410"))
    )
    (comp (ref "U11")
      (value "DNP")
      (footprint "eagle-import:QFN24G-0.5-4X4MM")
      (libsource (lib "eagle-import") (part "TRANSCEIVER-SX1261/2"))
    )
    (comp (ref "U13")
      (value "STTS751")
      (footprint "eagle-import:UDFN-6L")
      (libsource (lib "eagle-import") (part "SENSOR-STTS751"))
    )
    (comp (ref "U14")
      (value "N32G4FRKEQ7")
      (footprint "eagle-import:QFN32G-0.4-4X4MM")
      (libsource (lib "eagle-import") (part "MCU-N32G4FRKCQ7"))
    )
    (comp (ref "X1")
      (value "DSB221SDN")
      (footprint "eagle-import:X4-SMD-2.5X2.0X1.0MM")
      (libsource (lib "eagle-import") (part "CRYSTAL-OSCILLATOR-2520"))
    )
    (comp (ref "X2")
      (value "5MAA32000081TF80Q3")
      (footprint "eagle-import:X4-SMD-2.0X1.6X0.5MM")
      (libsource (lib "eagle-import") (part "CRYSTAL-4P-2016"))
    )
    (comp (ref "X3")
      (value "32.768kHz")
      (footprint "eagle-import:X2-SMD-3.2X1.5X0.55MM")
      (libsource (lib "eagle-import") (part "CRYSTAL-2P-3215"))
    )
  )
  (nets
    (net (code "1") (name "32MHZ") (class "Default")
      (node (ref "R37") (pin "2") (pinfunction "2_2") (pintype "passive"))
      (node (ref "R6") (pin "2") (pinfunction "2_2") (pintype "passive"))
      (node (ref "R9") (pin "2") (pinfunction "2_2") (pintype "passive"))
      (node (ref "X1") (pin "3") (pinfunction "OUT_3") (pintype "bidirectional"))
    )
    (net (code "2") (name "1302_CS") (class "Default")
      (node (ref "R33") (pin "2") (pinfunction "2_2") (pintype "passive"))
      (node (ref "R43") (pin "1") (pinfunction "1_1") (pintype "passive"))
      (node (ref "U1") (pin "1") (pinfunction "HOST_CSN_1") (pintype "bidirectional"))
      (node (ref "U14") (pin "13") (pinfunction "PC4_13") (pintype "bidirectional"))
    )
    (net (code "3") (name "1302_RESET") (class "Default")
      (node (ref "C1") (pin "2") (pinfunction "2_2") (pintype "passive"))
      (node (ref "D7") (pin "-") (pinfunction "-_-") (pintype "passive"))
      (node (ref "R1") (pin "2") (pinfunction "2_2") (pintype "passive"))
      (node (ref "U1") (pin "7") (pinfunction "RESET_7") (pintype "bidirectional"))
      (node (ref "U14") (pin "14") (pinfunction "PC5_14") (pintype "bidirectional"))
    )
    (net (code "4") (name "1302_RESET_HOST") (class "Default")
      (node (ref "D7") (pin "+") (pinfunction "+_+") (pintype "passive"))
      (node (ref "R59") (pin "1") (pinfunction "1_1") (pintype "passive"))
    )
    (net (code "5") (name "CONFIG_OK") (class "Default")
      (node (ref "R31") (pin "1") (pinfunction "1_1") (pintype "passive"))
      (node (ref "U1") (pin "66") (pinfunction "GPIO0_66") (pintype "bidirectional"))
    )
    (net (code "6") (name "CS_PCIE") (class "Default")
      (node (ref "J1") (pin "51") (pinfunction "51_51") (pintype "bidirectional"))
      (node (ref "R43") (pin "2") (pinfunction "2_2") (pintype "passive"))
    )
    (net (code "7") (name "DM") (class "Default")
      (node (ref "J1") (pin "36") (pinfunction "36_36") (pintype "bidirectional"))
      (node (ref "R66") (pin "1") (pinfunction "1_1") (pintype "passive"))
    )
    (net (code "8") (name "DP") (class "Default")
      (node (ref "J1") (pin "38") (pinfunction "38_38") (pintype "bidirectional"))
      (node (ref "R64") (pin "1") (pinfunction "1_1") (pintype "passive"))
    )
    (net (code "9") (name "FEM_CS") (class "Default")
      (node (ref "R14") (pin "2") (pinfunction "2_2") (pintype "passive"))
      (node (ref "R34") (pin "1") (pinfunction "1_1") (pintype "passive"))
      (node (ref "U1") (pin "10") (pinfunction "RADIO_CTRL0_10") (pintype "bidirectional"))
    )
    (net (code "10") (name "FEM_PA_ON") (class "Default")
      (node (ref "R15") (pin "2") (pinfunction "2_2") (pintype "passive"))
      (node (ref "U1") (pin "16") (pinfunction "RADIO_CTRL4_16") (pintype "bidirectional"))
    )
    (net (code "11") (name "GND_POWER") (class "Default")
      (node (ref "ANT1") (pin "GND1") (pinfunction "GND1_GND1") (pintype "bidirectional"))
      (node (ref "ANT1") (pin "GND2") (pinfunction "GND2_GND2") (pintype "bidirectional"))
      (node (ref "ANT2") (pin "GND1") (pinfunction "GND1_GND1") (pintype "bidirectional"))
      (node (ref "ANT2") (pin "GND2") (pinfunction "GND2_GND2") (pintype "bidirectional"))
      (node (ref "C12") (pin "1") (pinfunction "1_1") (pintype "passive"))
      (node (ref "C13") (pin "1") (pinfunction "1_1") (pintype "passive"))
      (node (ref "C15") (pin "2") (pinfunction "2_2") (pintype "passive"))
      (node (ref "C16") (pin "1") (pinfunction "1_1") (pintype "passive"))
      (node (ref "C17") (pin "1") (pinfunction "1_1") (pintype "passive"))
      (node (ref "C18") (pin "1") (pinfunction "1_1") (pintype "passive"))
      (node (ref "C19") (pin "1") (pinfunction "1_1") (pintype "passive"))
      (node (ref "C2") (pin "1") (pinfunction "1_1") (pintype "passive"))
      (node (ref "C20") (pin "1") (pinfunction "1_1") (pintype "passive"))
      (node (ref "C21") (pin "1") (pinfunction "1_1") (pintype "passive"))
      (node (ref "C22") (pin "1") (pinfunction "1_1") (pintype "passive"))
      (node (ref "C23") (pin "1") (pinfunction "1_1") (pintype "passive"))
      (node (ref "C24") (pin "1") (pinfunction "1_1") (pintype "passive"))
      (node (ref "C25") (pin "1") (pinfunction "1_1") (pintype "passive"))
      (node (ref "C26") (pin "1") (pinfunction "1_1") (pintype "passive"))
      (node (ref "C28") (pin "1") (pinfunction "1_1") (pintype "passive"))
      (node (ref "C29") (pin "1") (pinfunction "1_1") (pintype "passive"))
      (node (ref "C3") (pin "1") (pinfunction "1_1") (pintype "passive"))
      (node (ref "C30") (pin "1") (pinfunction "1_1") (pintype "passive"))
      (node (ref "C31") (pin "1") (pinfunction "1_1") (pintype "passive"))
      (node (ref "C34") (pin "1") (pinfunction "1_1") (pintype "passive"))
      (node (ref "C35") (pin "1") (pinfunction "1_1") (pintype "passive"))
      (node (ref "C36") (pin "1") (pinfunction "1_1") (pintype "passive"))
      (node (ref "C37") (pin "1") (pinfunction "1_1") (pintype "passive"))
      (node (ref "C39") (pin "1") (pinfunction "1_1") (pintype "passive"))
      (node (ref "C40") (pin "1") (pinfunction "1_1") (pintype "passive"))
      (node (ref "C41") (pin "1") (pinfunction "1_1") (pintype "passive"))
      (node (ref "C42") (pin "1") (pinfunction "1_1") (pintype "passive"))
      (node (ref "C43") (pin "1") (pinfunction "1_1") (pintype "passive"))
      (node (ref "C44") (pin "1") (pinfunction "1_1") (pintype "passive"))
      (node (ref "C45") (pin "1") (pinfunction "1_1") (pintype "passive"))
      (node (ref "C46") (pin "1") (pinfunction "1_1") (pintype "passive"))
      (node (ref "C47") (pin "1") (pinfunction "1_1") (pintype "passive"))
      (node (ref "C48") (pin "1") (pinfunction "1_1") (pintype "passive"))
      (node (ref "C49") (pin "1") (pinfunction "1_1") (pintype "passive"))
      (node (ref "C5") (pin "1") (pinfunction "1_1") (pintype "passive"))
      (node (ref "C50") (pin "1") (pinfunction "1_1") (pintype "passive"))
      (node (ref "C51") (pin "1") (pinfunction "1_1") (pintype "passive"))
      (node (ref "C52") (pin "1") (pinfunction "1_1") (pintype "passive"))
      (node (ref "C55") (pin "1") (pinfunction "1_1") (pintype "passive"))
      (node (ref "C56") (pin "1") (pinfunction "1_1") (pintype "passive"))
      (node (ref "C57") (pin "1") (pinfunction "1_1") (pintype "passive"))
      (node (ref "C58") (pin "1") (pinfunction "1_1") (pintype "passive"))
      (node (ref "C60") (pin "2") (pinfunction "2_2") (pintype "passive"))
      (node (ref "C61") (pin "2") (pinfunction "2_2") (pintype "passive"))
      (node (ref "C62") (pin "1") (pinfunction "1_1") (pintype "passive"))
      (node (ref "C63") (pin "2") (pinfunction "2_2") (pintype "passive"))
      (node (ref "C65") (pin "2") (pinfunction "2_2") (pintype "passive"))
      (node (ref "C67") (pin "2") (pinfunction "2_2") (pintype "passive"))
      (node (ref "C69") (pin "1") (pinfunction "1_1") (pintype "passive"))
      (node (ref "C7") (pin "1") (pinfunction "1_1") (pintype "passive"))
      (node (ref "C70") (pin "1") (pinfunction "1_1") (pintype "passive"))
      (node (ref "C71") (pin "1") (pinfunction "1_1") (pintype "passive"))
      (node (ref "C72") (pin "1") (pinfunction "1_1") (pintype "passive"))
      (node (ref "C73") (pin "2") (pinfunction "2_2") (pintype "passive"))
      (node (ref "C74") (pin "2") (pinfunction "2_2") (pintype "passive"))
      (node (ref "C76") (pin "1") (pinfunction "1_1") (pintype "passive"))
      (node (ref "C77") (pin "2") (pinfunction "2_2") (pintype "passive"))
      (node (ref "C78") (pin "2") (pinfunction "2_2") (pintype "passive"))
      (node (ref "C80") (pin "1") (pinfunction "1_1") (pintype "passive"))
      (node (ref "C81") (pin "2") (pinfunction "2_2") (pintype "passive"))
      (node (ref "C82") (pin "2") (pinfunction "2_2") (pintype "passive"))
      (node (ref "C83") (pin "1") (pinfunction "1_1") (pintype "passive"))
      (node (ref "C84") (pin "2") (pinfunction "2_2") (pintype "passive"))
      (node (ref "C85") (pin "1") (pinfunction "1_1") (pintype "passive"))
      (node (ref "C86") (pin "1") (pinfunction "1_1") (pintype "passive"))
      (node (ref "C87") (pin "1") (pinfunction "1_1") (pintype "passive"))
      (node (ref "C88") (pin "1") (pinfunction "1_1") (pintype "passive"))
      (node (ref "C89") (pin "1") (pinfunction "1_1") (pintype "passive"))
      (node (ref "C9") (pin "1") (pinfunction "1_1") (pintype "passive"))
      (node (ref "C90") (pin "1") (pinfunction "1_1") (pintype "passive"))
      (node (ref "C92") (pin "1") (pinfunction "1_1") (pintype "passive"))
      (node (ref "D1") (pin "-") (pinfunction "-_-") (pintype "passive"))
      (node (ref "D2") (pin "-") (pinfunction "-_-") (pintype "passive"))
      (node (ref "D3") (pin "-") (pinfunction "-_-") (pintype "passive"))
      (node (ref "D4") (pin "-") (pinfunction "-_-") (pintype "passive"))
      (node (ref "D5") (pin "1") (pinfunction "1_1") (pintype "bidirectional"))
      (node (ref "D6") (pin "1") (pinfunction "1_1") (pintype "bidirectional"))
      (node (ref "J1") (pin "15") (pinfunction "GND_15") (pintype "bidirectional"))
      (node (ref "J1") (pin "18") (pinfunction "GND_18") (pintype "bidirectional"))
      (node (ref "J1") (pin "21") (pinfunction "GND_21") (pintype "bidirectional"))
      (node (ref "J1") (pin "26") (pinfunction "GND_26") (pintype "bidirectional"))
      (node (ref "J1") (pin "27") (pinfunction "GND_27") (pintype "bidirectional"))
      (node (ref "J1") (pin "29") (pinfunction "GND_29") (pintype "bidirectional"))
      (node (ref "J1") (pin "34") (pinfunction "GND_34") (pintype "bidirectional"))
      (node (ref "J1") (pin "35") (pinfunction "GND_35") (pintype "bidirectional"))
      (node (ref "J1") (pin "37") (pinfunction "GND_37") (pintype "bidirectional"))
      (node (ref "J1") (pin "4") (pinfunction "GND_4") (pintype "bidirectional"))
      (node (ref "J1") (pin "40") (pinfunction "GND_40") (pintype "bidirectional"))
      (node (ref "J1") (pin "43") (pinfunction "GND_43") (pintype "bidirectional"))
      (node (ref "J1") (pin "50") (pinfunction "GND_50") (pintype "bidirectional"))
      (node (ref "J1") (pin "9") (pinfunction "GND_9") (pintype "bidirectional"))
      (node (ref "J1") (pin "S1") (pinfunction "GND_S1") (pintype "bidirectional"))
      (node (ref "J1") (pin "S2") (pinfunction "GND_S2") (pintype "bidirectional"))
      (node (ref "Q10") (pin "2") (pinfunction "S_2") (pintype "passive"))
      (node (ref "R1") (pin "1") (pinfunction "1_1") (pintype "passive"))
      (node (ref "R11") (pin "1") (pinfunction "1_1") (pintype "passive"))
      (node (ref "R12") (pin "1") (pinfunction "1_1") (pintype "passive"))
      (node (ref "R2") (pin "2") (pinfunction "2_2") (pintype "passive"))
      (node (ref "R4") (pin "1") (pinfunction "1_1") (pintype "passive"))
      (node (ref "R53") (pin "1") (pinfunction "1_1") (pintype "passive"))
      (node (ref "R53") (pin "2") (pinfunction "2_2") (pintype "passive"))
      (node (ref "R54") (pin "1") (pinfunction "1_1") (pintype "passive"))
      (node (ref "R54") (pin "2") (pinfunction "2_2") (pintype "passive"))
      (node (ref "R55") (pin "1") (pinfunction "1_1") (pintype "passive"))
      (node (ref "R55") (pin "2") (pinfunction "2_2") (pintype "passive"))
      (node (ref "R57") (pin "2") (pinfunction "2_2") (pintype "passive"))
      (node (ref "R73") (pin "1") (pinfunction "1_1") (pintype "passive"))
      (node (ref "R74") (pin "1") (pinfunction "1_1") (pintype "passive"))
      (node (ref "R74") (pin "2") (pinfunction "2_2") (pintype "passive"))
      (node (ref "R87") (pin "1") (pinfunction "1_1") (pintype "passive"))
      (node (ref "S1") (pin "1") (pinfunction "S1_1") (pintype "bidirectional"))
      (node (ref "TP16") (pin "1") (pinfunction "T_1") (pintype "bidirectional"))
      (node (ref "TP17") (pin "1") (pinfunction "T_1") (pintype "bidirectional"))
      (node (ref "TP3") (pin "T") (pinfunction "T_T") (pintype "bidirectional"))
      (node (ref "U1") (pin "15") (pinfunction "GND_15") (pintype "bidirectional"))
      (node (ref "U1") (pin "20") (pinfunction "SP_VALID_20") (pintype "bidirectional"))
      (node (ref "U1") (pin "24") (pinfunction "GND_24") (pintype "bidirectional"))
      (node (ref "U1") (pin "25") (pinfunction "GND_25") (pintype "bidirectional"))
      (node (ref "U1") (pin "39") (pinfunction "GND_39") (pintype "bidirectional"))
      (node (ref "U1") (pin "46") (pinfunction "GND_46") (pintype "bidirectional"))
      (node (ref "U1") (pin "55") (pinfunction "GND_55") (pintype "bidirectional"))
      (node (ref "U1") (pin "6") (pinfunction "GND_6") (pintype "bidirectional"))
      (node (ref "U1") (pin "62") (pinfunction "GND_62") (pintype "bidirectional"))
      (node (ref "U1") (pin "69") (pinfunction "GND_69") (pintype "bidirectional"))
      (node (ref "U1") (pin "9") (pinfunction "GND_9") (pintype "bidirectional"))
      (node (ref "U10") (pin "1") (pinfunction "GND_1") (pintype "bidirectional"))
      (node (ref "U10") (pin "3") (pinfunction "GND_3") (pintype "bidirectional"))
      (node (ref "U10") (pin "4") (pinfunction "GND_4") (pintype "bidirectional"))
      (node (ref "U10") (pin "6") (pinfunction "GND_6") (pintype "bidirectional"))
      (node (ref "U11") (pin "2") (pinfunction "GND_2") (pintype "bidirectional"))
      (node (ref "U11") (pin "20") (pinfunction "GND_20") (pintype "bidirectional"))
      (node (ref "U11") (pin "5") (pinfunction "GND_5") (pintype "bidirectional"))
      (node (ref "U11") (pin "8") (pinfunction "GND_8") (pintype "bidirectional"))
      (node (ref "U11") (pin "PAD") (pinfunction "PAD_PAD") (pintype "bidirectional"))
      (node (ref "U13") (pin "4") (pinfunction "ADDR/~{THERM}_4") (pintype "bidirectional"))
      (node (ref "U13") (pin "5") (pinfunction "GND_5") (pintype "bidirectional"))
      (node (ref "U14") (pin "23") (pinfunction "VSS_2_23") (pintype "bidirectional"))
      (node (ref "U14") (pin "31") (pinfunction "VSS_3_31") (pintype "bidirectional"))
      (node (ref "U14") (pin "33") (pinfunction "PAD_33") (pintype "bidirectional"))
      (node (ref "U14") (pin "6") (pinfunction "VSSA_6") (pintype "bidirectional"))
      (node (ref "U2") (pin "1") (pinfunction "GND_1") (pintype "bidirectional"))
      (node (ref "U2") (pin "3") (pinfunction "GND_3") (pintype "bidirectional"))
      (node (ref "U2") (pin "4") (pinfunction "GND_4") (pintype "bidirectional"))
      (node (ref "U2") (pin "6") (pinfunction "GND_6") (pintype "bidirectional"))
      (node (ref "U5") (pin "20") (pinfunction "GND_20") (pintype "bidirectional"))
      (node (ref "U5") (pin "7") (pinfunction "GND_7") (pintype "bidirectional"))
      (node (ref "U5") (pin "PAD") (pinfunction "PAD_PAD") (pintype "bidirectional"))
      (node (ref "U6") (pin "4") (pinfunction "PGND_4") (pintype "bidirectional"))
      (node (ref "U6") (pin "6") (pinfunction "AGND_6") (pintype "bidirectional"))
      (node (ref "U7") (pin "20") (pinfunction "GND_20") (pintype "bidirectional"))
      (node (ref "U7") (pin "7") (pinfunction "GND_7") (pintype "bidirectional"))
      (node (ref "U7") (pin "PAD") (pinfunction "PAD_PAD") (pintype "bidirectional"))
      (node (ref "U8") (pin "1") (pinfunction "GND_1") (pintype "bidirectional"))
      (node (ref "U8") (pin "3") (pinfunction "GND_3") (pintype "bidirectional"))
      (node (ref "U8") (pin "4") (pinfunction "GND_4") (pintype "bidirectional"))
      (node (ref "U8") (pin "6") (pinfunction "GND_6") (pintype "bidirectional"))
      (node (ref "U9") (pin "10") (pinfunction "GND_10") (pintype "bidirectional"))
      (node (ref "U9") (pin "12") (pinfunction "GND_12") (pintype "bidirectional"))
      (node (ref "U9") (pin "17") (pinfunction "EPAD_17") (pintype "bidirectional"))
      (node (ref "X1") (pin "2") (pinfunction "GND_2") (pintype "bidirectional"))
      (node (ref "X2") (pin "2") (pinfunction "GND_2") (pintype "bidirectional"))
      (node (ref "X2") (pin "4") (pinfunction "GND_4") (pintype "bidirectional"))
    )
    (net (code "12") (name "I2C_SCL") (class "Default")
      (node (ref "R68") (pin "2") (pinfunction "2_2") (pintype "passive"))
      (node (ref "R81") (pin "1") (pinfunction "1_1") (pintype "passive"))
      (node (ref "U13") (pin "1") (pinfunction "SCL_1") (pintype "bidirectional"))
      (node (ref "U14") (pin "15") (pinfunction "PB10_15") (pintype "bidirectional"))
    )
    (net (code "13") (name "I2C_SDA") (class "Default")
      (node (ref "R58") (pin "2") (pinfunction "2_2") (pintype "passive"))
      (node (ref "R75") (pin "1") (pinfunction "1_1") (pintype "passive"))
      (node (ref "U13") (pin "6") (pinfunction "SDA_6") (pintype "bidirectional"))
      (node (ref "U14") (pin "16") (pinfunction "PB11_16") (pintype "bidirectional"))
    )
    (net (code "14") (name "MCU_RESET") (class "Default")
      (node (ref "C85") (pin "2") (pinfunction "2_2") (pintype "passive"))
      (node (ref "R71") (pin "2") (pinfunction "2_2") (pintype "passive"))
      (node (ref "R77") (pin "1") (pinfunction "1_1") (pintype "passive"))
      (node (ref "TP5") (pin "T") (pinfunction "T_T") (pintype "bidirectional"))
      (node (ref "U14") (pin "5") (pinfunction "NRST_5") (pintype "bidirectional"))
    )
    (net (code "15") (name "MISO") (class "Default")
      (node (ref "R44") (pin "1") (pinfunction "1_1") (pintype "passive"))
      (node (ref "R45") (pin "1") (pinfunction "1_1") (pintype "passive"))
      (node (ref "U1") (pin "2") (pinfunction "HOST_MISO_2") (pintype "bidirectional"))
      (node (ref "U11") (pin "16") (pinfunction "MISO_16") (pintype "bidirectional"))
    )
    (net (code "16") (name "MISO_A") (class "Default")
      (node (ref "U1") (pin "42") (pinfunction "RADIO_A_MISO_42") (pintype "bidirectional"))
      (node (ref "U5") (pin "16") (pinfunction "MISO_16") (pintype "bidirectional"))
    )
    (net (code "17") (name "MISO_B") (class "Default")
      (node (ref "U1") (pin "33") (pinfunction "RADIO_B_MISO_33") (pintype "bidirectional"))
      (node (ref "U7") (pin "16") (pinfunction "MISO_16") (pintype "bidirectional"))
    )
    (net (code "18") (name "MISO_PCIE") (class "Default")
      (node (ref "R39") (pin "1") (pinfunction "1_1") (pintype "passive"))
      (node (ref "R44") (pin "2") (pinfunction "2_2") (pintype "passive"))
    )
    (net (code "19") (name "MOSI") (class "Default")
      (node (ref "R40") (pin "2") (pinfunction "2_2") (pintype "passive"))
      (node (ref "R46") (pin "1") (pinfunction "1_1") (pintype "passive"))
      (node (ref "R48") (pin "1") (pinfunction "1_1") (pintype "passive"))
      (node (ref "R5") (pin "2") (pinfunction "2_2") (pintype "passive"))
    )
    (net (code "20") (name "MOSI_A") (class "Default")
      (node (ref "U1") (pin "67") (pinfunction "RADIO_A_MOSI_67") (pintype "bidirectional"))
      (node (ref "U5") (pin "17") (pinfunction "MOSI_17") (pintype "bidirectional"))
    )
    (net (code "21") (name "MOSI_B") (class "Default")
      (node (ref "U1") (pin "19") (pinfunction "RADIO_B_MOSI_19") (pintype "bidirectional"))
      (node (ref "U7") (pin "17") (pinfunction "MOSI_17") (pintype "bidirectional"))
    )
    (net (code "22") (name "MOSI_PCIE") (class "Default")
      (node (ref "J1") (pin "49") (pinfunction "49_49") (pintype "bidirectional"))
      (node (ref "R46") (pin "2") (pinfunction "2_2") (pintype "passive"))
    )
    (net (code "23") (name "Net-(ANT1-PadD)") (class "Default")
      (node (ref "ANT1") (pin "D") (pinfunction "D_D") (pintype "bidirectional"))
      (node (ref "C64") (pin "2") (pinfunction "2_2") (pintype "passive"))
      (node (ref "D5") (pin "2") (pinfunction "2_2") (pintype "bidirectional"))
    )
    (net (code "24") (name "Net-(ANT2-PadD)") (class "Default")
      (node (ref "ANT2") (pin "D") (pinfunction "D_D") (pintype "bidirectional"))
      (node (ref "C79") (pin "2") (pinfunction "2_2") (pintype "passive"))
      (node (ref "D6") (pin "2") (pinfunction "2_2") (pintype "bidirectional"))
    )
    (net (code "25") (name "Net-(C1-Pad1)") (class "Default")
      (node (ref "C1") (pin "1") (pinfunction "1_1") (pintype "passive"))
      (node (ref "R80") (pin "1") (pinfunction "1_1") (pintype "passive"))
    )
    (net (code "26") (name "Net-(C4-Pad1)") (class "Default")
      (node (ref "C4") (pin "1") (pinfunction "1_1") (pintype "passive"))
      (node (ref "C8") (pin "2") (pinfunction "2_2") (pintype "passive"))
      (node (ref "R12") (pin "2") (pinfunction "2_2") (pintype "passive"))
    )
    (net (code "27") (name "Net-(C14-Pad2)") (class "Default")
      (node (ref "C14") (pin "2") (pinfunction "2_2") (pintype "passive"))
      (node (ref "R6") (pin "1") (pinfunction "1_1") (pintype "passive"))
    )
    (net (code "28") (name "Net-(C38-Pad2)") (class "Default")
      (node (ref "C38") (pin "2") (pinfunction "2_2") (pintype "passive"))
      (node (ref "R9") (pin "1") (pinfunction "1_1") (pintype "passive"))
    )
    (net (code "29") (name "Net-(C53-Pad2)") (class "Default")
      (node (ref "C53") (pin "2") (pinfunction "2_2") (pintype "passive"))
      (node (ref "C54") (pin "1") (pinfunction "1_1") (pintype "passive"))
      (node (ref "C7") (pin "2") (pinfunction "2_2") (pintype "passive"))
      (node (ref "L10") (pin "2") (pinfunction "2_2") (pintype "passive"))
    )
    (net (code "30") (name "Net-(C54-Pad2)") (class "Default")
      (node (ref "C54") (pin "2") (pinfunction "2_2") (pintype "passive"))
      (node (ref "L11") (pin "1") (pinfunction "1_1") (pintype "passive"))
    )
    (net (code "31") (name "Net-(C56-Pad2)") (class "Default")
      (node (ref "C56") (pin "2") (pinfunction "2_2") (pintype "passive"))
      (node (ref "C57") (pin "2") (pinfunction "2_2") (pintype "passive"))
      (node (ref "L16") (pin "1") (pinfunction "1_1") (pintype "passive"))
      (node (ref "L8") (pin "2") (pinfunction "2_2") (pintype "passive"))
    )
    (net (code "32") (name "Net-(C59-Pad1)") (class "Default")
      (node (ref "C59") (pin "1") (pinfunction "1_1") (pintype "passive"))
      (node (ref "C91") (pin "2") (pinfunction "2_2") (pintype "passive"))
    )
    (net (code "33") (name "Net-(C61-Pad1)") (class "Default")
      (node (ref "C61") (pin "1") (pinfunction "1_1") (pintype "passive"))
      (node (ref "C91") (pin "1") (pinfunction "1_1") (pintype "passive"))
      (node (ref "L17") (pin "2") (pinfunction "2_2") (pintype "passive"))
      (node (ref "L24") (pin "1") (pinfunction "1_1") (pintype "passive"))
    )
    (net (code "34") (name "Net-(C64-Pad1)") (class "Default")
      (node (ref "C64") (pin "1") (pinfunction "1_1") (pintype "passive"))
      (node (ref "C82") (pin "1") (pinfunction "1_1") (pintype "passive"))
      (node (ref "L24") (pin "2") (pinfunction "2_2") (pintype "passive"))
    )
    (net (code "35") (name "Net-(C66-Pad2)") (class "Default")
      (node (ref "C66") (pin "2") (pinfunction "2_2") (pintype "passive"))
      (node (ref "R37") (pin "1") (pinfunction "1_1") (pintype "passive"))
    )
    (net (code "36") (name "Net-(C68-Pad1)") (class "Default")
      (node (ref "C68") (pin "1") (pinfunction "1_1") (pintype "passive"))
      (node (ref "C74") (pin "1") (pinfunction "1_1") (pintype "passive"))
      (node (ref "C75") (pin "2") (pinfunction "2_2") (pintype "passive"))
    )
    (net (code "37") (name "Net-(C77-Pad1)") (class "Default")
      (node (ref "C77") (pin "1") (pinfunction "1_1") (pintype "passive"))
      (node (ref "L21") (pin "1") (pinfunction "1_1") (pintype "passive"))
      (node (ref "R62") (pin "2") (pinfunction "2_2") (pintype "passive"))
    )
    (net (code "38") (name "Net-(C78-Pad1)") (class "Default")
      (node (ref "C78") (pin "1") (pinfunction "1_1") (pintype "passive"))
      (node (ref "C79") (pin "1") (pinfunction "1_1") (pintype "passive"))
      (node (ref "L21") (pin "2") (pinfunction "2_2") (pintype "passive"))
    )
    (net (code "39") (name "Net-(D1-Pad+)") (class "Default")
      (node (ref "D1") (pin "+") (pinfunction "+_+") (pintype "passive"))
      (node (ref "R30") (pin "2") (pinfunction "2_2") (pintype "passive"))
    )
    (net (code "40") (name "Net-(D2-Pad+)") (class "Default")
      (node (ref "D2") (pin "+") (pinfunction "+_+") (pintype "passive"))
      (node (ref "R31") (pin "2") (pinfunction "2_2") (pintype "passive"))
    )
    (net (code "41") (name "Net-(D3-Pad+)") (class "Default")
      (node (ref "D3") (pin "+") (pinfunction "+_+") (pintype "passive"))
      (node (ref "R32") (pin "2") (pinfunction "2_2") (pintype "passive"))
    )
    (net (code "42") (name "Net-(D4-Pad+)") (class "Default")
      (node (ref "D4") (pin "+") (pinfunction "+_+") (pintype "passive"))
      (node (ref "R47") (pin "2") (pinfunction "2_2") (pintype "passive"))
    )
    (net (code "43") (name "Net-(J1-Pad30)") (class "Default")
      (node (ref "J1") (pin "30") (pinfunction "30_30") (pintype "bidirectional"))
      (node (ref "R81") (pin "2") (pinfunction "2_2") (pintype "passive"))
    )
    (net (code "44") (name "Net-(J1-Pad32)") (class "Default")
      (node (ref "J1") (pin "32") (pinfunction "32_32") (pintype "bidirectional"))
      (node (ref "R75") (pin "2") (pinfunction "2_2") (pintype "passive"))
    )
    (net (code "45") (name "Net-(J1-Pad47)") (class "Default")
      (node (ref "J1") (pin "47") (pinfunction "47_47") (pintype "bidirectional"))
      (node (ref "R39") (pin "2") (pinfunction "2_2") (pintype "passive"))
    )
    (net (code "46") (name "Net-(Q10-D)") (class "Default")
      (node (ref "Q10") (pin "3") (pinfunction "D_3") (pintype "passive"))
      (node (ref "Q8") (pin "1") (pinfunction "G_1") (pintype "passive"))
      (node (ref "R78") (pin "2") (pinfunction "2_2") (pintype "passive"))
    )
    (net (code "47") (name "Net-(Q10-G)") (class "Default")
      (node (ref "C92") (pin "2") (pinfunction "2_2") (pintype "passive"))
      (node (ref "Q10") (pin "1") (pinfunction "G_1") (pintype "passive"))
      (node (ref "R79") (pin "2") (pinfunction "2_2") (pintype "passive"))
    )
    (net (code "48") (name "Net-(U1-HOST_MOSI)") (class "Default")
      (node (ref "R5") (pin "1") (pinfunction "1_1") (pintype "passive"))
      (node (ref "U1") (pin "3") (pinfunction "HOST_MOSI_3") (pintype "bidirectional"))
    )
    (net (code "49") (name "Net-(U1-HOST_SCK)") (class "Default")
      (node (ref "R10") (pin "1") (pinfunction "1_1") (pintype "passive"))
      (node (ref "U1") (pin "4") (pinfunction "HOST_SCK_4") (pintype "bidirectional"))
    )
    (net (code "50") (name "Net-(U1-RADIO_A_CLK_I)") (class "Default")
      (node (ref "R25") (pin "1") (pinfunction "1_1") (pintype "passive"))
      (node (ref "U1") (pin "43") (pinfunction "RADIO_A_CLK_I_43") (pintype "bidirectional"))
    )
    (net (code "51") (name "Net-(U1-RADIO_A_IQ0)") (class "Default")
      (node (ref "R26") (pin "1") (pinfunction "1_1") (pintype "passive"))
      (node (ref "U1") (pin "44") (pinfunction "RADIO_A_IQ0_44") (pintype "bidirectional"))
    )
    (net (code "52") (name "Net-(U1-RADIO_A_IQ1)") (class "Default")
      (node (ref "R27") (pin "1") (pinfunction "1_1") (pintype "passive"))
      (node (ref "U1") (pin "45") (pinfunction "RADIO_A_IQ1_45") (pintype "bidirectional"))
    )
    (net (code "53") (name "Net-(U1-RADIO_A_IQ2)") (class "Default")
      (node (ref "R29") (pin "1") (pinfunction "1_1") (pintype "passive"))
      (node (ref "U1") (pin "49") (pinfunction "RADIO_A_IQ2_49") (pintype "bidirectional"))
    )
    (net (code "54") (name "Net-(U1-RADIO_A_IQ3)") (class "Default")
      (node (ref "R24") (pin "1") (pinfunction "1_1") (pintype "passive"))
      (node (ref "U1") (pin "41") (pinfunction "RADIO_A_IQ3_41") (pintype "bidirectional"))
    )
    (net (code "55") (name "Net-(U1-RADIO_A_IQ4)") (class "Default")
      (node (ref "R28") (pin "1") (pinfunction "1_1") (pintype "passive"))
      (node (ref "U1") (pin "48") (pinfunction "RADIO_A_IQ4_48") (pintype "bidirectional"))
    )
    (net (code "56") (name "Net-(U1-RADIO_B_CLK_I)") (class "Default")
      (node (ref "R19") (pin "1") (pinfunction "1_1") (pintype "passive"))
      (node (ref "U1") (pin "34") (pinfunction "RADIO_B_CLK_I_34") (pintype "bidirectional"))
    )
    (net (code "57") (name "Net-(U1-RADIO_B_IQ0)") (class "Default")
      (node (ref "R20") (pin "1") (pinfunction "1_1") (pintype "passive"))
      (node (ref "U1") (pin "35") (pinfunction "RADIO_B_IQ0_35") (pintype "bidirectional"))
    )
    (net (code "58") (name "Net-(U1-RADIO_B_IQ1)") (class "Default")
      (node (ref "R21") (pin "1") (pinfunction "1_1") (pintype "passive"))
      (node (ref "U1") (pin "36") (pinfunction "RADIO_B_IQ1_36") (pintype "bidirectional"))
    )
    (net (code "59") (name "Net-(U1-RADIO_B_IQ2)") (class "Default")
      (node (ref "R23") (pin "1") (pinfunction "1_1") (pintype "passive"))
      (node (ref "U1") (pin "38") (pinfunction "RADIO_B_IQ2_38") (pintype "bidirectional"))
    )
    (net (code "60") (name "Net-(U1-RADIO_B_IQ3)") (class "Default")
      (node (ref "R18") (pin "1") (pinfunction "1_1") (pintype "passive"))
      (node (ref "U1") (pin "32") (pinfunction "RADIO_B_IQ3_32") (pintype "bidirectional"))
    )
    (net (code "61") (name "Net-(U1-RADIO_B_IQ4)") (class "Default")
      (node (ref "R22") (pin "1") (pinfunction "1_1") (pintype "passive"))
      (node (ref "U1") (pin "37") (pinfunction "RADIO_B_IQ4_37") (pintype "bidirectional"))
    )
    (net (code "62") (name "Net-(U2-IN)") (class "Default")
      (node (ref "C11") (pin "1") (pinfunction "1_1") (pintype "passive"))
      (node (ref "U2") (pin "2") (pinfunction "IN_2") (pintype "bidirectional"))
    )
    (net (code "63") (name "Net-(U2-OUT)") (class "Default")
      (node (ref "C10") (pin "1") (pinfunction "1_1") (pintype "passive"))
      (node (ref "C6") (pin "1") (pinfunction "1_1") (pintype "passive"))
      (node (ref "C75") (pin "1") (pinfunction "1_1") (pintype "passive"))
      (node (ref "U2") (pin "5") (pinfunction "OUT_5") (pintype "bidirectional"))
    )
    (net (code "64") (name "Net-(U5-DCC_SW)") (class "Default")
      (node (ref "L6") (pin "2") (pinfunction "2_2") (pintype "passive"))
      (node (ref "U5") (pin "8") (pinfunction "DCC_SW_8") (pintype "bidirectional"))
    )
    (net (code "65") (name "Net-(U5-VREG)") (class "Default")
      (node (ref "C34") (pin "2") (pinfunction "2_2") (pintype "passive"))
      (node (ref "L6") (pin "1") (pinfunction "1_1") (pintype "passive"))
      (node (ref "L7") (pin "2") (pinfunction "2_2") (pintype "passive"))
      (node (ref "U5") (pin "6") (pinfunction "VREG_6") (pintype "bidirectional"))
    )
    (net (code "66") (name "Net-(U5-VR_PA)") (class "Default")
      (node (ref "C36") (pin "2") (pinfunction "2_2") (pintype "passive"))
      (node (ref "C37") (pin "2") (pinfunction "2_2") (pintype "passive"))
      (node (ref "L9") (pin "2") (pinfunction "2_2") (pintype "passive"))
      (node (ref "U5") (pin "1") (pinfunction "VR_PA_1") (pintype "bidirectional"))
    )
    (net (code "67") (name "Net-(U5-XTA)") (class "Default")
      (node (ref "C14") (pin "1") (pinfunction "1_1") (pintype "passive"))
      (node (ref "U5") (pin "3") (pinfunction "XTA_3") (pintype "bidirectional"))
    )
    (net (code "68") (name "Net-(U6-EN)") (class "Default")
      (node (ref "R82") (pin "2") (pinfunction "2_2") (pintype "passive"))
      (node (ref "U6") (pin "8") (pinfunction "EN_8") (pintype "bidirectional"))
    )
    (net (code "69") (name "Net-(U6-FB)") (class "Default")
      (node (ref "R83") (pin "1") (pinfunction "1_1") (pintype "passive"))
      (node (ref "R87") (pin "2") (pinfunction "2_2") (pintype "passive"))
      (node (ref "U6") (pin "7") (pinfunction "FB_7") (pintype "bidirectional"))
    )
    (net (code "70") (name "Net-(U6-PG)") (class "Default")
      (node (ref "TP15") (pin "T") (pinfunction "T_T") (pintype "bidirectional"))
      (node (ref "U6") (pin "1") (pinfunction "PG_1") (pintype "bidirectional"))
    )
    (net (code "71") (name "Net-(U6-SW)") (class "Default")
      (node (ref "L5") (pin "1") (pinfunction "1_1") (pintype "passive"))
      (node (ref "U6") (pin "3") (pinfunction "SW_3") (pintype "bidirectional"))
    )
    (net (code "72") (name "Net-(U7-DCC_SW)") (class "Default")
      (node (ref "L14") (pin "2") (pinfunction "2_2") (pintype "passive"))
      (node (ref "U7") (pin "8") (pinfunction "DCC_SW_8") (pintype "bidirectional"))
    )
    (net (code "73") (name "Net-(U7-VREG)") (class "Default")
      (node (ref "C46") (pin "2") (pinfunction "2_2") (pintype "passive"))
      (node (ref "L14") (pin "1") (pinfunction "1_1") (pintype "passive"))
      (node (ref "L15") (pin "2") (pinfunction "2_2") (pintype "passive"))
      (node (ref "U7") (pin "6") (pinfunction "VREG_6") (pintype "bidirectional"))
    )
    (net (code "74") (name "Net-(U7-XTA)") (class "Default")
      (node (ref "C38") (pin "1") (pinfunction "1_1") (pintype "passive"))
      (node (ref "U7") (pin "3") (pinfunction "XTA_3") (pintype "bidirectional"))
    )
    (net (code "75") (name "Net-(U8-IN)") (class "Default")
      (node (ref "C2") (pin "2") (pinfunction "2_2") (pintype "passive"))
      (node (ref "L11") (pin "2") (pinfunction "2_2") (pintype "passive"))
      (node (ref "U8") (pin "2") (pinfunction "IN_2") (pintype "bidirectional"))
    )
    (net (code "76") (name "Net-(U8-OUT)") (class "Default")
      (node (ref "C8") (pin "1") (pinfunction "1_1") (pintype "passive"))
      (node (ref "R11") (pin "2") (pinfunction "2_2") (pintype "passive"))
      (node (ref "U8") (pin "5") (pinfunction "OUT_5") (pintype "bidirectional"))
    )
    (net (code "77") (name "Net-(U9-ANT)") (class "Default")
      (node (ref "C59") (pin "2") (pinfunction "2_2") (pintype "passive"))
      (node (ref "C60") (pin "1") (pinfunction "1_1") (pintype "passive"))
      (node (ref "L17") (pin "1") (pinfunction "1_1") (pintype "passive"))
      (node (ref "U9") (pin "9") (pinfunction "ANT_9") (pintype "bidirectional"))
    )
    (net (code "78") (name "Net-(U9-CPS)") (class "Default")
      (node (ref "C17") (pin "2") (pinfunction "2_2") (pintype "passive"))
      (node (ref "R15") (pin "1") (pinfunction "1_1") (pintype "passive"))
      (node (ref "U9") (pin "5") (pinfunction "CPS_5") (pintype "bidirectional"))
    )
    (net (code "79") (name "Net-(U9-CSD)") (class "Default")
      (node (ref "C16") (pin "2") (pinfunction "2_2") (pintype "passive"))
      (node (ref "R14") (pin "1") (pinfunction "1_1") (pintype "passive"))
      (node (ref "U9") (pin "4") (pinfunction "CSD_4") (pintype "bidirectional"))
    )
    (net (code "80") (name "Net-(U9-CTX)") (class "Default")
      (node (ref "C18") (pin "2") (pinfunction "2_2") (pintype "passive"))
      (node (ref "R16") (pin "1") (pinfunction "1_1") (pintype "passive"))
      (node (ref "U9") (pin "6") (pinfunction "CTX_6") (pintype "bidirectional"))
    )
    (net (code "81") (name "Net-(U9-PA_OUT)") (class "Default")
      (node (ref "L2") (pin "1") (pinfunction "1_1") (pintype "passive"))
      (node (ref "L8") (pin "1") (pinfunction "1_1") (pintype "passive"))
      (node (ref "U9") (pin "13") (pinfunction "PA_OUT_13") (pintype "bidirectional"))
    )
    (net (code "82") (name "Net-(U9-RX)") (class "Default")
      (node (ref "C11") (pin "2") (pinfunction "2_2") (pintype "passive"))
      (node (ref "U9") (pin "2") (pinfunction "RX_2") (pintype "bidirectional"))
    )
    (net (code "83") (name "Net-(U9-RX_FLT)") (class "Default")
      (node (ref "R69") (pin "1") (pinfunction "1_1") (pintype "passive"))
      (node (ref "U9") (pin "8") (pinfunction "RX_FLT_8") (pintype "bidirectional"))
    )
    (net (code "84") (name "Net-(U9-TX)") (class "Default")
      (node (ref "C4") (pin "2") (pinfunction "2_2") (pintype "passive"))
      (node (ref "U9") (pin "1") (pinfunction "TX_1") (pintype "bidirectional"))
    )
    (net (code "85") (name "Net-(U9-TX_IN)") (class "Default")
      (node (ref "C58") (pin "2") (pinfunction "2_2") (pintype "passive"))
      (node (ref "L16") (pin "2") (pinfunction "2_2") (pintype "passive"))
      (node (ref "U9") (pin "11") (pinfunction "TX_IN_11") (pintype "bidirectional"))
    )
    (net (code "86") (name "Net-(U9-VCC1)") (class "Default")
      (node (ref "L1") (pin "1") (pinfunction "1_1") (pintype "passive"))
      (node (ref "U9") (pin "16") (pinfunction "VCC1_16") (pintype "bidirectional"))
    )
    (net (code "87") (name "Net-(U10-IN)") (class "Default")
      (node (ref "R62") (pin "1") (pinfunction "1_1") (pintype "passive"))
      (node (ref "R69") (pin "2") (pinfunction "2_2") (pintype "passive"))
      (node (ref "U10") (pin "2") (pinfunction "IN_2") (pintype "bidirectional"))
    )
    (net (code "88") (name "Net-(U10-OUT)") (class "Default")
      (node (ref "U10") (pin "5") (pinfunction "OUT_5") (pintype "bidirectional"))
      (node (ref "U9") (pin "7") (pinfunction "LNA_IN_7") (pintype "bidirectional"))
    )
    (net (code "89") (name "Net-(U11-DCC_SW)") (class "Default")
      (node (ref "L20") (pin "2") (pinfunction "2_2") (pintype "passive"))
      (node (ref "U11") (pin "9") (pinfunction "DCC_SW_9") (pintype "bidirectional"))
    )
    (net (code "90") (name "Net-(U11-MOSI)") (class "Default")
      (node (ref "R40") (pin "1") (pinfunction "1_1") (pintype "passive"))
      (node (ref "U11") (pin "17") (pinfunction "MOSI_17") (pintype "bidirectional"))
    )
    (net (code "91") (name "Net-(U11-SCK)") (class "Default")
      (node (ref "R41") (pin "1") (pinfunction "1_1") (pintype "passive"))
      (node (ref "U11") (pin "18") (pinfunction "SCK_18") (pintype "bidirectional"))
    )
    (net (code "92") (name "Net-(U11-VDD_IN)") (class "Default")
      (node (ref "C65") (pin "1") (pinfunction "1_1") (pintype "passive"))
      (node (ref "R36") (pin "2") (pinfunction "2_2") (pintype "passive"))
      (node (ref "U11") (pin "1") (pinfunction "VDD_IN_1") (pintype "bidirectional"))
    )
    (net (code "93") (name "Net-(U11-VREG)") (class "Default")
      (node (ref "C63") (pin "1") (pinfunction "1_1") (pintype "passive"))
      (node (ref "L20") (pin "1") (pinfunction "1_1") (pintype "passive"))
      (node (ref "U11") (pin "7") (pinfunction "VREG_7") (pintype "bidirectional"))
    )
    (net (code "94") (name "Net-(U11-XTA)") (class "Default")
      (node (ref "C66") (pin "1") (pinfunction "1_1") (pintype "passive"))
      (node (ref "U11") (pin "3") (pinfunction "XTA_3") (pintype "bidirectional"))
    )
    (net (code "95") (name "Net-(U13-~{EVENT})") (class "Default")
      (node (ref "R65") (pin "2") (pinfunction "2_2") (pintype "passive"))
      (node (ref "U13") (pin "2") (pinfunction "~{EVENT}_2") (pintype "bidirectional"))
    )
    (net (code "96") (name "Net-(U14-BOOT0)") (class "Default")
      (node (ref "R56") (pin "2") (pinfunction "2_2") (pintype "passive"))
      (node (ref "R57") (pin "1") (pinfunction "1_1") (pintype "passive"))
      (node (ref "U14") (pin "30") (pinfunction "BOOT0_30") (pintype "bidirectional"))
    )
    (net (code "97") (name "Net-(U14-PA4)") (class "Default")
      (node (ref "R72") (pin "2") (pinfunction "2_2") (pintype "passive"))
      (node (ref "R73") (pin "2") (pinfunction "2_2") (pintype "passive"))
      (node (ref "U14") (pin "9") (pinfunction "PA4_9") (pintype "bidirectional"))
    )
    (net (code "98") (name "Net-(U14-PA9)") (class "Default")
      (node (ref "TP12") (pin "T") (pinfunction "T_T") (pintype "bidirectional"))
      (node (ref "U14") (pin "18") (pinfunction "PA9_18") (pintype "bidirectional"))
    )
    (net (code "99") (name "Net-(U14-PA10)") (class "Default")
      (node (ref "TP11") (pin "T") (pinfunction "T_T") (pintype "bidirectional"))
      (node (ref "U14") (pin "19") (pinfunction "PA10_19") (pintype "bidirectional"))
    )
    (net (code "100") (name "Net-(U14-PA11-USB_DM)") (class "Default")
      (node (ref "R66") (pin "2") (pinfunction "2_2") (pintype "passive"))
      (node (ref "U14") (pin "20") (pinfunction "PA11-USB_DM_20") (pintype "bidirectional"))
    )
    (net (code "101") (name "Net-(U14-PA12-USB_DP)") (class "Default")
      (node (ref "R64") (pin "2") (pinfunction "2_2") (pintype "passive"))
      (node (ref "U14") (pin "21") (pinfunction "PA12-USB_DP_21") (pintype "bidirectional"))
    )
    (net (code "102") (name "Net-(U14-PC14-OSC32_IN)") (class "Default")
      (node (ref "C81") (pin "1") (pinfunction "1_1") (pintype "passive"))
      (node (ref "U14") (pin "1") (pinfunction "PC14-OSC32_IN_1") (pintype "bidirectional"))
      (node (ref "X3") (pin "2") (pinfunction "2_2") (pintype "passive"))
    )
    (net (code "103") (name "Net-(U14-PC15-OSC32_OUT)") (class "Default")
      (node (ref "C84") (pin "1") (pinfunction "1_1") (pintype "passive"))
      (node (ref "U14") (pin "2") (pinfunction "PC15-OSC32_OUT_2") (pintype "bidirectional"))
      (node (ref "X3") (pin "1") (pinfunction "1_1") (pintype "passive"))
    )
    (net (code "104") (name "Net-(U14-PD0-OSC_IN)") (class "Default")
      (node (ref "C15") (pin "1") (pinfunction "1_1") (pintype "passive"))
      (node (ref "U14") (pin "3") (pinfunction "PD0-OSC_IN_3") (pintype "bidirectional"))
      (node (ref "X2") (pin "1") (pinfunction "X1_1") (pintype "bidirectional"))
    )
    (net (code "105") (name "Net-(U14-PD1-OSC_OUT)") (class "Default")
      (node (ref "R7") (pin "2") (pinfunction "2_2") (pintype "passive"))
      (node (ref "U14") (pin "4") (pinfunction "PD1-OSC_OUT_4") (pintype "bidirectional"))
    )
    (net (code "106") (name "Net-(X1-ENABLE)") (class "Default")
      (node (ref "R3") (pin "1") (pinfunction "1_1") (pintype "passive"))
      (node (ref "R4") (pin "2") (pinfunction "2_2") (pintype "passive"))
      (node (ref "X1") (pin "1") (pinfunction "ENABLE_1") (pintype "bidirectional"))
    )
    (net (code "107") (name "Net-(X1-VDD)") (class "Default")
      (node (ref "C62") (pin "2") (pinfunction "2_2") (pintype "passive"))
      (node (ref "L4") (pin "1") (pinfunction "1_1") (pintype "bidirectional"))
      (node (ref "R3") (pin "2") (pinfunction "2_2") (pintype "passive"))
      (node (ref "X1") (pin "4") (pinfunction "VDD_4") (pintype "bidirectional"))
    )
    (net (code "108") (name "Net-(X2-X2)") (class "Default")
      (node (ref "C26") (pin "2") (pinfunction "2_2") (pintype "passive"))
      (node (ref "R7") (pin "1") (pinfunction "1_1") (pintype "passive"))
      (node (ref "X2") (pin "3") (pinfunction "X2_3") (pintype "bidirectional"))
    )
    (net (code "109") (name "PPS") (class "Default")
      (node (ref "J1") (pin "19") (pinfunction "19_19") (pintype "bidirectional"))
      (node (ref "TP2") (pin "T") (pinfunction "T_T") (pintype "bidirectional"))
      (node (ref "U1") (pin "8") (pinfunction "PPS_8") (pintype "bidirectional"))
      (node (ref "U14") (pin "27") (pinfunction "PB3_27") (pintype "bidirectional"))
    )
    (net (code "110") (name "RADIO_A_CLK_32M") (class "Default")
      (node (ref "R25") (pin "2") (pinfunction "2_2") (pintype "passive"))
      (node (ref "R72") (pin "1") (pinfunction "1_1") (pintype "passive"))
      (node (ref "U5") (pin "14") (pinfunction "BUSY_14") (pintype "bidirectional"))
    )
    (net (code "111") (name "RADIO_A_CLK_O") (class "Default")
      (node (ref "R28") (pin "2") (pinfunction "2_2") (pintype "passive"))
      (node (ref "U5") (pin "11") (pinfunction "DIO5_11") (pintype "bidirectional"))
    )
    (net (code "112") (name "RADIO_A_CSN") (class "Default")
      (node (ref "U1") (pin "68") (pinfunction "RADIO_A_CSN_68") (pintype "bidirectional"))
      (node (ref "U5") (pin "19") (pinfunction "NSS_19") (pintype "bidirectional"))
    )
    (net (code "113") (name "RADIO_A_IQ_0") (class "Default")
      (node (ref "R26") (pin "2") (pinfunction "2_2") (pintype "passive"))
      (node (ref "U5") (pin "13") (pinfunction "DIO1_13") (pintype "bidirectional"))
    )
    (net (code "114") (name "RADIO_A_IQ_1") (class "Default")
      (node (ref "R27") (pin "2") (pinfunction "2_2") (pintype "passive"))
      (node (ref "U5") (pin "12") (pinfunction "DIO2_12") (pintype "bidirectional"))
    )
    (net (code "115") (name "RADIO_A_IQ_2") (class "Default")
      (node (ref "R29") (pin "2") (pinfunction "2_2") (pintype "passive"))
      (node (ref "U5") (pin "5") (pinfunction "DIO3_5") (pintype "bidirectional"))
    )
    (net (code "116") (name "RADIO_A_IQ_3") (class "Default")
      (node (ref "R24") (pin "2") (pinfunction "2_2") (pintype "passive"))
      (node (ref "U5") (pin "21") (pinfunction "DIO4_21") (pintype "bidirectional"))
    )
    (net (code "117") (name "RADIO_A_RESET") (class "Default")
      (node (ref "U1") (pin "13") (pinfunction "RADIO_CTRL3_13") (pintype "bidirectional"))
      (node (ref "U5") (pin "15") (pinfunction "NRESET_15") (pintype "bidirectional"))
    )
    (net (code "118") (name "RADIO_A_RFIN") (class "Default")
      (node (ref "C6") (pin "2") (pinfunction "2_2") (pintype "passive"))
      (node (ref "L12") (pin "2") (pinfunction "2_2") (pintype "passive"))
      (node (ref "U5") (pin "23") (pinfunction "RFI_N_23") (pintype "bidirectional"))
    )
    (net (code "119") (name "RADIO_A_RFIP") (class "Default")
      (node (ref "C5") (pin "2") (pinfunction "2_2") (pintype "passive"))
      (node (ref "L12") (pin "1") (pinfunction "1_1") (pintype "passive"))
      (node (ref "U5") (pin "22") (pinfunction "RFI_P_22") (pintype "bidirectional"))
    )
    (net (code "120") (name "RADIO_B_CLK_32M") (class "Default")
      (node (ref "R19") (pin "2") (pinfunction "2_2") (pintype "passive"))
      (node (ref "U7") (pin "14") (pinfunction "BUSY_14") (pintype "bidirectional"))
    )
    (net (code "121") (name "RADIO_B_CLK_O") (class "Default")
      (node (ref "R22") (pin "2") (pinfunction "2_2") (pintype "passive"))
      (node (ref "U7") (pin "11") (pinfunction "DIO5_11") (pintype "bidirectional"))
    )
    (net (code "122") (name "RADIO_B_CSN") (class "Default")
      (node (ref "U1") (pin "18") (pinfunction "RADIO_B_CSN_18") (pintype "bidirectional"))
      (node (ref "U7") (pin "19") (pinfunction "NSS_19") (pintype "bidirectional"))
    )
    (net (code "123") (name "RADIO_B_IQ0") (class "Default")
      (node (ref "R20") (pin "2") (pinfunction "2_2") (pintype "passive"))
      (node (ref "U7") (pin "13") (pinfunction "DIO1_13") (pintype "bidirectional"))
    )
    (net (code "124") (name "RADIO_B_IQ_1") (class "Default")
      (node (ref "R21") (pin "2") (pinfunction "2_2") (pintype "passive"))
      (node (ref "U7") (pin "12") (pinfunction "DIO2_12") (pintype "bidirectional"))
    )
    (net (code "125") (name "RADIO_B_IQ_2") (class "Default")
      (node (ref "R23") (pin "2") (pinfunction "2_2") (pintype "passive"))
      (node (ref "U7") (pin "5") (pinfunction "DIO3_5") (pintype "bidirectional"))
    )
    (net (code "126") (name "RADIO_B_IQ_3") (class "Default")
      (node (ref "R18") (pin "2") (pinfunction "2_2") (pintype "passive"))
      (node (ref "U7") (pin "21") (pinfunction "DIO4_21") (pintype "bidirectional"))
    )
    (net (code "127") (name "RADIO_B_RESET") (class "Default")
      (node (ref "U1") (pin "28") (pinfunction "RADIO_CTRL9_28") (pintype "bidirectional"))
      (node (ref "U7") (pin "15") (pinfunction "NRESET_15") (pintype "bidirectional"))
    )
    (net (code "128") (name "RADIO_B_RFIN") (class "Default")
      (node (ref "C10") (pin "2") (pinfunction "2_2") (pintype "passive"))
      (node (ref "L13") (pin "2") (pinfunction "2_2") (pintype "passive"))
      (node (ref "U7") (pin "23") (pinfunction "RFI_N_23") (pintype "bidirectional"))
    )
    (net (code "129") (name "RADIO_B_RFIP") (class "Default")
      (node (ref "C9") (pin "2") (pinfunction "2_2") (pintype "passive"))
      (node (ref "L13") (pin "1") (pinfunction "1_1") (pintype "passive"))
      (node (ref "U7") (pin "22") (pinfunction "RFI_P_22") (pintype "bidirectional"))
    )
    (net (code "130") (name "RESET_PCIE") (class "Default")
      (node (ref "J1") (pin "22") (pinfunction "22_22") (pintype "bidirectional"))
      (node (ref "R59") (pin "2") (pinfunction "2_2") (pintype "passive"))
      (node (ref "R77") (pin "2") (pinfunction "2_2") (pintype "passive"))
    )
    (net (code "131") (name "RFO") (class "Default")
      (node (ref "C53") (pin "1") (pinfunction "1_1") (pintype "passive"))
      (node (ref "L10") (pin "1") (pinfunction "1_1") (pintype "passive"))
      (node (ref "L9") (pin "1") (pinfunction "1_1") (pintype "passive"))
      (node (ref "U5") (pin "24") (pinfunction "RFO_24") (pintype "bidirectional"))
    )
    (net (code "132") (name "RX_ON") (class "Default")
      (node (ref "R32") (pin "1") (pinfunction "1_1") (pintype "passive"))
      (node (ref "U1") (pin "59") (pinfunction "GPIO4_59") (pintype "bidirectional"))
    )
    (net (code "133") (name "SCK") (class "Default")
      (node (ref "R10") (pin "2") (pinfunction "2_2") (pintype "passive"))
      (node (ref "R41") (pin "2") (pinfunction "2_2") (pintype "passive"))
      (node (ref "R49") (pin "1") (pinfunction "1_1") (pintype "passive"))
      (node (ref "R50") (pin "1") (pinfunction "1_1") (pintype "passive"))
    )
    (net (code "134") (name "SCK_A") (class "Default")
      (node (ref "U1") (pin "65") (pinfunction "RADIO_A_SCK_65") (pintype "bidirectional"))
      (node (ref "U5") (pin "18") (pinfunction "SCK_18") (pintype "bidirectional"))
    )
    (net (code "135") (name "SCK_B") (class "Default")
      (node (ref "U1") (pin "21") (pinfunction "RADIO_B_SCK_21") (pintype "bidirectional"))
      (node (ref "U7") (pin "18") (pinfunction "SCK_18") (pintype "bidirectional"))
    )
    (net (code "136") (name "SCLK_PCIE") (class "Default")
      (node (ref "J1") (pin "45") (pinfunction "45_45") (pintype "bidirectional"))
      (node (ref "R49") (pin "2") (pinfunction "2_2") (pintype "passive"))
    )
    (net (code "137") (name "STM32_MISO") (class "Default")
      (node (ref "R45") (pin "2") (pinfunction "2_2") (pintype "passive"))
      (node (ref "U14") (pin "11") (pinfunction "PA6_11") (pintype "bidirectional"))
    )
    (net (code "138") (name "STM32_MOSI") (class "Default")
      (node (ref "R48") (pin "2") (pinfunction "2_2") (pintype "passive"))
      (node (ref "U14") (pin "12") (pinfunction "PA7_12") (pintype "bidirectional"))
    )
    (net (code "139") (name "STM32_SCK") (class "Default")
      (node (ref "R50") (pin "2") (pinfunction "2_2") (pintype "passive"))
      (node (ref "U14") (pin "10") (pinfunction "PA5_10") (pintype "bidirectional"))
    )
    (net (code "140") (name "SWCLK") (class "Default")
      (node (ref "TP7") (pin "T") (pinfunction "T_T") (pintype "bidirectional"))
      (node (ref "U14") (pin "25") (pinfunction "PA14-SWCLK_25") (pintype "bidirectional"))
    )
    (net (code "141") (name "SWDIO") (class "Default")
      (node (ref "TP8") (pin "T") (pinfunction "T_T") (pintype "bidirectional"))
      (node (ref "U14") (pin "22") (pinfunction "PA13-SWDIO_22") (pintype "bidirectional"))
    )
    (net (code "142") (name "SX1261_IO3") (class "Default")
      (node (ref "TP9") (pin "T") (pinfunction "T_T") (pintype "bidirectional"))
      (node (ref "U11") (pin "6") (pinfunction "DIO3_6") (pintype "bidirectional"))
    )
    (net (code "143") (name "SX1261_RFIN") (class "Default")
      (node (ref "C68") (pin "2") (pinfunction "2_2") (pintype "passive"))
      (node (ref "L22") (pin "2") (pinfunction "2_2") (pintype "passive"))
      (node (ref "U11") (pin "22") (pinfunction "RFI_N_22") (pintype "bidirectional"))
    )
    (net (code "144") (name "SX1261_RFIP") (class "Default")
      (node (ref "C73") (pin "1") (pinfunction "1_1") (pintype "passive"))
      (node (ref "L22") (pin "1") (pinfunction "1_1") (pintype "passive"))
      (node (ref "U11") (pin "21") (pinfunction "RFI_P_21") (pintype "bidirectional"))
    )
    (net (code "145") (name "SX1262_BUSY") (class "Default")
      (node (ref "R67") (pin "1") (pinfunction "1_1") (pintype "passive"))
      (node (ref "U11") (pin "14") (pinfunction "BUSY_14") (pintype "bidirectional"))
      (node (ref "U14") (pin "8") (pinfunction "PA0_WKUP_8") (pintype "bidirectional"))
    )
    (net (code "146") (name "SX1262_BUSY_PCIE") (class "Default")
      (node (ref "J1") (pin "8") (pinfunction "8_8") (pintype "bidirectional"))
      (node (ref "R67") (pin "2") (pinfunction "2_2") (pintype "passive"))
    )
    (net (code "147") (name "SX1262_CS") (class "Default")
      (node (ref "R42") (pin "1") (pinfunction "1_1") (pintype "passive"))
      (node (ref "R51") (pin "1") (pinfunction "1_1") (pintype "passive"))
      (node (ref "U11") (pin "19") (pinfunction "NSS_19") (pintype "bidirectional"))
      (node (ref "U14") (pin "29") (pinfunction "PB5_29") (pintype "bidirectional"))
    )
    (net (code "148") (name "SX1262_CS_PCIE") (class "Default")
      (node (ref "J1") (pin "25") (pinfunction "25_25") (pintype "bidirectional"))
      (node (ref "R51") (pin "2") (pinfunction "2_2") (pintype "passive"))
    )
    (net (code "149") (name "SX1262_IO1") (class "Default")
      (node (ref "R61") (pin "1") (pinfunction "1_1") (pintype "passive"))
      (node (ref "U1") (pin "54") (pinfunction "GPIO7_54") (pintype "bidirectional"))
      (node (ref "U11") (pin "13") (pinfunction "DIO1_13") (pintype "bidirectional"))
      (node (ref "U14") (pin "28") (pinfunction "PB4_28") (pintype "bidirectional"))
    )
    (net (code "150") (name "SX1262_IO1_PCIE") (class "Default")
      (node (ref "J1") (pin "33") (pinfunction "33_33") (pintype "bidirectional"))
      (node (ref "R61") (pin "2") (pinfunction "2_2") (pintype "passive"))
    )
    (net (code "151") (name "SX1262_IO2") (class "Default")
      (node (ref "R63") (pin "1") (pinfunction "1_1") (pintype "passive"))
      (node (ref "U11") (pin "12") (pinfunction "DIO2_12") (pintype "bidirectional"))
    )
    (net (code "152") (name "SX1262_IO2_PCIE") (class "Default")
      (node (ref "J1") (pin "31") (pinfunction "31_31") (pintype "bidirectional"))
      (node (ref "R2") (pin "1") (pinfunction "1_1") (pintype "passive"))
      (node (ref "R63") (pin "2") (pinfunction "2_2") (pintype "passive"))
    )
    (net (code "153") (name "SX1262_RST") (class "Default")
      (node (ref "R38") (pin "1") (pinfunction "1_1") (pintype "passive"))
      (node (ref "R60") (pin "1") (pinfunction "1_1") (pintype "passive"))
      (node (ref "U11") (pin "15") (pinfunction "NRESET_15") (pintype "bidirectional"))
      (node (ref "U14") (pin "17") (pinfunction "PA8_17") (pintype "bidirectional"))
    )
    (net (code "154") (name "SX1262_RST_PCIE") (class "Default")
      (node (ref "J1") (pin "10") (pinfunction "10_10") (pintype "bidirectional"))
      (node (ref "R60") (pin "2") (pinfunction "2_2") (pintype "passive"))
    )
    (net (code "155") (name "SX1302_GPIO8") (class "Default")
      (node (ref "U1") (pin "53") (pinfunction "GPIO8_53") (pintype "bidirectional"))
      (node (ref "U14") (pin "26") (pinfunction "PA15_26") (pintype "bidirectional"))
    )
    (net (code "156") (name "TX_ON") (class "Default")
      (node (ref "R30") (pin "1") (pinfunction "1_1") (pintype "passive"))
      (node (ref "U1") (pin "63") (pinfunction "GPIO2_63") (pintype "bidirectional"))
    )
    (net (code "157") (name "TX_RX_SW") (class "Default")
      (node (ref "R16") (pin "2") (pinfunction "2_2") (pintype "passive"))
      (node (ref "U1") (pin "12") (pinfunction "RADIO_CTRL2_12") (pintype "bidirectional"))
    )
    (net (code "158") (name "VCCIO") (class "Default")
      (node (ref "C19") (pin "2") (pinfunction "2_2") (pintype "passive"))
      (node (ref "C20") (pin "2") (pinfunction "2_2") (pintype "passive"))
      (node (ref "C25") (pin "2") (pinfunction "2_2") (pintype "passive"))
      (node (ref "C28") (pin "2") (pinfunction "2_2") (pintype "passive"))
      (node (ref "C3") (pin "2") (pinfunction "2_2") (pintype "passive"))
      (node (ref "C41") (pin "2") (pinfunction "2_2") (pintype "passive"))
      (node (ref "C42") (pin "2") (pinfunction "2_2") (pintype "passive"))
      (node (ref "C45") (pin "2") (pinfunction "2_2") (pintype "passive"))
      (node (ref "C47") (pin "2") (pinfunction "2_2") (pintype "passive"))
      (node (ref "C76") (pin "2") (pinfunction "2_2") (pintype "passive"))
      (node (ref "C80") (pin "2") (pinfunction "2_2") (pintype "passive"))
      (node (ref "C83") (pin "2") (pinfunction "2_2") (pintype "passive"))
      (node (ref "C86") (pin "2") (pinfunction "2_2") (pintype "passive"))
      (node (ref "C87") (pin "2") (pinfunction "2_2") (pintype "passive"))
      (node (ref "C88") (pin "2") (pinfunction "2_2") (pintype "passive"))
      (node (ref "C89") (pin "2") (pinfunction "2_2") (pintype "passive"))
      (node (ref "C90") (pin "2") (pinfunction "2_2") (pintype "passive"))
      (node (ref "Q8") (pin "3") (pinfunction "D_3") (pintype "passive"))
      (node (ref "R33") (pin "1") (pinfunction "1_1") (pintype "passive"))
      (node (ref "R34") (pin "2") (pinfunction "2_2") (pintype "passive"))
      (node (ref "R56") (pin "1") (pinfunction "1_1") (pintype "passive"))
      (node (ref "R58") (pin "1") (pinfunction "1_1") (pintype "passive"))
      (node (ref "R65") (pin "1") (pinfunction "1_1") (pintype "passive"))
      (node (ref "R68") (pin "1") (pinfunction "1_1") (pintype "passive"))
      (node (ref "R71") (pin "1") (pinfunction "1_1") (pintype "passive"))
      (node (ref "R80") (pin "2") (pinfunction "2_2") (pintype "passive"))
      (node (ref "TP1") (pin "T") (pinfunction "T_T") (pintype "bidirectional"))
      (node (ref "U1") (pin "14") (pinfunction "VCC_IO_14") (pintype "bidirectional"))
      (node (ref "U1") (pin "30") (pinfunction "VCC_IO_30") (pintype "bidirectional"))
      (node (ref "U1") (pin "47") (pinfunction "VCC_IO_47") (pintype "bidirectional"))
      (node (ref "U1") (pin "61") (pinfunction "VCC_IO_61") (pintype "bidirectional"))
      (node (ref "U13") (pin "3") (pinfunction "VDD_3") (pintype "bidirectional"))
      (node (ref "U14") (pin "24") (pinfunction "VDD_2_24") (pintype "bidirectional"))
      (node (ref "U14") (pin "32") (pinfunction "VDD_3_32") (pintype "bidirectional"))
      (node (ref "U14") (pin "7") (pinfunction "VDDA_7") (pintype "bidirectional"))
    )
    (net (code "159") (name "VCC_1V2") (class "Default")
      (node (ref "C12") (pin "2") (pinfunction "2_2") (pintype "passive"))
      (node (ref "C13") (pin "2") (pinfunction "2_2") (pintype "passive"))
      (node (ref "C23") (pin "2") (pinfunction "2_2") (pintype "passive"))
      (node (ref "C24") (pin "2") (pinfunction "2_2") (pintype "passive"))
      (node (ref "C29") (pin "2") (pinfunction "2_2") (pintype "passive"))
      (node (ref "C40") (pin "2") (pinfunction "2_2") (pintype "passive"))
      (node (ref "C43") (pin "2") (pinfunction "2_2") (pintype "passive"))
      (node (ref "C44") (pin "2") (pinfunction "2_2") (pintype "passive"))
      (node (ref "C71") (pin "2") (pinfunction "2_2") (pintype "passive"))
      (node (ref "C72") (pin "2") (pinfunction "2_2") (pintype "passive"))
      (node (ref "L5") (pin "2") (pinfunction "2_2") (pintype "passive"))
      (node (ref "R79") (pin "1") (pinfunction "1_1") (pintype "passive"))
      (node (ref "R83") (pin "2") (pinfunction "2_2") (pintype "passive"))
      (node (ref "TP14") (pin "T") (pinfunction "T_T") (pintype "bidirectional"))
      (node (ref "U1") (pin "23") (pinfunction "VCC_CORE_23") (pintype "bidirectional"))
      (node (ref "U1") (pin "40") (pinfunction "VCC_CORE_40") (pintype "bidirectional"))
      (node (ref "U1") (pin "5") (pinfunction "VCC_CORE_5") (pintype "bidirectional"))
      (node (ref "U1") (pin "56") (pinfunction "VCC_CORE_56") (pintype "bidirectional"))
      (node (ref "U6") (pin "5") (pinfunction "OUT_5") (pintype "bidirectional"))
    )
    (net (code "160") (name "VCC_FEM") (class "Default")
      (node (ref "C49") (pin "2") (pinfunction "2_2") (pintype "passive"))
      (node (ref "C50") (pin "2") (pinfunction "2_2") (pintype "passive"))
      (node (ref "C51") (pin "2") (pinfunction "2_2") (pintype "passive"))
      (node (ref "C52") (pin "2") (pinfunction "2_2") (pintype "passive"))
      (node (ref "C55") (pin "2") (pinfunction "2_2") (pintype "passive"))
      (node (ref "FB1") (pin "2") (pinfunction "2_2") (pintype "bidirectional"))
      (node (ref "L1") (pin "2") (pinfunction "2_2") (pintype "passive"))
      (node (ref "L2") (pin "2") (pinfunction "2_2") (pintype "passive"))
      (node (ref "U9") (pin "15") (pinfunction "VCC0_15") (pintype "bidirectional"))
    )
    (net (code "161") (name "VCC_RADIO") (class "Default")
      (node (ref "C21") (pin "2") (pinfunction "2_2") (pintype "passive"))
      (node (ref "C22") (pin "2") (pinfunction "2_2") (pintype "passive"))
      (node (ref "C35") (pin "2") (pinfunction "2_2") (pintype "passive"))
      (node (ref "C39") (pin "2") (pinfunction "2_2") (pintype "passive"))
      (node (ref "C48") (pin "2") (pinfunction "2_2") (pintype "passive"))
      (node (ref "C67") (pin "1") (pinfunction "1_1") (pintype "passive"))
      (node (ref "FB3") (pin "2") (pinfunction "2_2") (pintype "bidirectional"))
      (node (ref "L15") (pin "1") (pinfunction "1_1") (pintype "passive"))
      (node (ref "L4") (pin "2") (pinfunction "2_2") (pintype "bidirectional"))
      (node (ref "L7") (pin "1") (pinfunction "1_1") (pintype "passive"))
      (node (ref "R36") (pin "1") (pinfunction "1_1") (pintype "passive"))
      (node (ref "R38") (pin "2") (pinfunction "2_2") (pintype "passive"))
      (node (ref "R42") (pin "2") (pinfunction "2_2") (pintype "passive"))
      (node (ref "TP10") (pin "T") (pinfunction "T_T") (pintype "bidirectional"))
      (node (ref "U11") (pin "10") (pinfunction "VBAT_10") (pintype "bidirectional"))
      (node (ref "U11") (pin "11") (pinfunction "VBAT_IO_11") (pintype "bidirectional"))
      (node (ref "U5") (pin "10") (pinfunction "VBAT_DIO_10") (pintype "bidirectional"))
      (node (ref "U5") (pin "2") (pinfunction "VDD_IN_2") (pintype "bidirectional"))
      (node (ref "U5") (pin "9") (pinfunction "VBAT_RF_9") (pintype "bidirectional"))
      (node (ref "U7") (pin "10") (pinfunction "VBAT_DIO_10") (pintype "bidirectional"))
      (node (ref "U7") (pin "2") (pinfunction "VDD_IN_2") (pintype "bidirectional"))
      (node (ref "U7") (pin "9") (pinfunction "VBAT_RF_9") (pintype "bidirectional"))
    )
    (net (code "162") (name "VIN") (class "Default")
      (node (ref "C30") (pin "2") (pinfunction "2_2") (pintype "passive"))
      (node (ref "C31") (pin "2") (pinfunction "2_2") (pintype "passive"))
      (node (ref "C69") (pin "2") (pinfunction "2_2") (pintype "passive"))
      (node (ref "C70") (pin "2") (pinfunction "2_2") (pintype "passive"))
      (node (ref "FB1") (pin "1") (pinfunction "1_1") (pintype "bidirectional"))
      (node (ref "FB3") (pin "1") (pinfunction "1_1") (pintype "bidirectional"))
      (node (ref "J1") (pin "2") (pinfunction "3V3_2") (pintype "bidirectional"))
      (node (ref "J1") (pin "24") (pinfunction "3V3_24") (pintype "bidirectional"))
      (node (ref "J1") (pin "39") (pinfunction "3V3_39") (pintype "bidirectional"))
      (node (ref "J1") (pin "41") (pinfunction "3V3_41") (pintype "bidirectional"))
      (node (ref "J1") (pin "52") (pinfunction "3V3_52") (pintype "bidirectional"))
      (node (ref "Q8") (pin "2") (pinfunction "S_2") (pintype "passive"))
      (node (ref "R47") (pin "1") (pinfunction "1_1") (pintype "passive"))
      (node (ref "R78") (pin "1") (pinfunction "1_1") (pintype "passive"))
      (node (ref "R82") (pin "1") (pinfunction "1_1") (pintype "passive"))
      (node (ref "TP4") (pin "T") (pinfunction "T_T") (pintype "bidirectional"))
      (node (ref "U6") (pin "2") (pinfunction "VIN_2") (pintype "bidirectional"))
    )
    (net (code "163") (name "unconnected-(J1-1V5-Pad6)") (class "Default")
      (node (ref "J1") (pin "6") (pinfunction "1V5_6") (pintype "bidirectional"))
    )
    (net (code "164") (name "unconnected-(J1-1V5-Pad28)") (class "Default")
      (node (ref "J1") (pin "28") (pinfunction "1V5_28") (pintype "bidirectional"))
    )
    (net (code "165") (name "unconnected-(J1-1V5-Pad48)") (class "Default")
      (node (ref "J1") (pin "48") (pinfunction "1V5_48") (pintype "bidirectional"))
    )
    (net (code "166") (name "unconnected-(J1-Pad1)") (class "Default")
      (node (ref "J1") (pin "1") (pinfunction "1_1") (pintype "bidirectional"))
    )
    (net (code "167") (name "unconnected-(J1-Pad3)") (class "Default")
      (node (ref "J1") (pin "3") (pinfunction "3_3") (pintype "bidirectional"))
    )
    (net (code "168") (name "unconnected-(J1-Pad5)") (class "Default")
      (node (ref "J1") (pin "5") (pinfunction "5_5") (pintype "bidirectional"))
    )
    (net (code "169") (name "unconnected-(J1-Pad7)") (class "Default")
      (node (ref "J1") (pin "7") (pinfunction "7_7") (pintype "bidirectional"))
    )
    (net (code "170") (name "unconnected-(J1-Pad11)") (class "Default")
      (node (ref "J1") (pin "11") (pinfunction "11_11") (pintype "bidirectional"))
    )
    (net (code "171") (name "unconnected-(J1-Pad12)") (class "Default")
      (node (ref "J1") (pin "12") (pinfunction "12_12") (pintype "bidirectional"))
    )
    (net (code "172") (name "unconnected-(J1-Pad13)") (class "Default")
      (node (ref "J1") (pin "13") (pinfunction "13_13") (pintype "bidirectional"))
    )
    (net (code "173") (name "unconnected-(J1-Pad14)") (class "Default")
      (node (ref "J1") (pin "14") (pinfunction "14_14") (pintype "bidirectional"))
    )
    (net (code "174") (name "unconnected-(J1-Pad16)") (class "Default")
      (node (ref "J1") (pin "16") (pinfunction "16_16") (pintype "bidirectional"))
    )
    (net (code "175") (name "unconnected-(J1-Pad17)") (class "Default")
      (node (ref "J1") (pin "17") (pinfunction "17_17") (pintype "bidirectional"))
    )
    (net (code "176") (name "unconnected-(J1-Pad20)") (class "Default")
      (node (ref "J1") (pin "20") (pinfunction "20_20") (pintype "bidirectional"))
    )
    (net (code "177") (name "unconnected-(J1-Pad23)") (class "Default")
      (node (ref "J1") (pin "23") (pinfunction "23_23") (pintype "bidirectional"))
    )
    (net (code "178") (name "unconnected-(J1-Pad42)") (class "Default")
      (node (ref "J1") (pin "42") (pinfunction "42_42") (pintype "bidirectional"))
    )
    (net (code "179") (name "unconnected-(J1-Pad44)") (class "Default")
      (node (ref "J1") (pin "44") (pinfunction "44_44") (pintype "bidirectional"))
    )
    (net (code "180") (name "unconnected-(J1-Pad46)") (class "Default")
      (node (ref "J1") (pin "46") (pinfunction "46_46") (pintype "bidirectional"))
    )
    (net (code "181") (name "unconnected-(U1-GPIO1-Pad64)") (class "Default")
      (node (ref "U1") (pin "64") (pinfunction "GPIO1_64") (pintype "bidirectional"))
    )
    (net (code "182") (name "unconnected-(U1-GPIO3-Pad60)") (class "Default")
      (node (ref "U1") (pin "60") (pinfunction "GPIO3_60") (pintype "bidirectional"))
    )
    (net (code "183") (name "unconnected-(U1-GPIO5-Pad58)") (class "Default")
      (node (ref "U1") (pin "58") (pinfunction "GPIO5_58") (pintype "bidirectional"))
    )
    (net (code "184") (name "unconnected-(U1-GPIO6-Pad57)") (class "Default")
      (node (ref "U1") (pin "57") (pinfunction "GPIO6_57") (pintype "bidirectional"))
    )
    (net (code "185") (name "unconnected-(U1-GPIO9-Pad52)") (class "Default")
      (node (ref "U1") (pin "52") (pinfunction "GPIO9_52") (pintype "bidirectional"))
    )
    (net (code "186") (name "unconnected-(U1-GPIO10-Pad51)") (class "Default")
      (node (ref "U1") (pin "51") (pinfunction "GPIO10_51") (pintype "bidirectional"))
    )
    (net (code "187") (name "unconnected-(U1-GPIO11-Pad50)") (class "Default")
      (node (ref "U1") (pin "50") (pinfunction "GPIO11_50") (pintype "bidirectional"))
    )
    (net (code "188") (name "unconnected-(U1-RADIO_CTRL1-Pad11)") (class "Default")
      (node (ref "U1") (pin "11") (pinfunction "RADIO_CTRL1_11") (pintype "bidirectional"))
    )
    (net (code "189") (name "unconnected-(U1-RADIO_CTRL5-Pad17)") (class "Default")
      (node (ref "U1") (pin "17") (pinfunction "RADIO_CTRL5_17") (pintype "bidirectional"))
    )
    (net (code "190") (name "unconnected-(U1-RADIO_CTRL6-Pad22)") (class "Default")
      (node (ref "U1") (pin "22") (pinfunction "RADIO_CTRL6_22") (pintype "bidirectional"))
    )
    (net (code "191") (name "unconnected-(U1-RADIO_CTRL7-Pad26)") (class "Default")
      (node (ref "U1") (pin "26") (pinfunction "RADIO_CTRL7_26") (pintype "bidirectional"))
    )
    (net (code "192") (name "unconnected-(U1-RADIO_CTRL8-Pad27)") (class "Default")
      (node (ref "U1") (pin "27") (pinfunction "RADIO_CTRL8_27") (pintype "bidirectional"))
    )
    (net (code "193") (name "unconnected-(U1-RADIO_CTRL10-Pad29)") (class "Default")
      (node (ref "U1") (pin "29") (pinfunction "RADIO_CTRL10_29") (pintype "bidirectional"))
    )
    (net (code "194") (name "unconnected-(U1-RADIO_CTRL11-Pad31)") (class "Default")
      (node (ref "U1") (pin "31") (pinfunction "RADIO_CTRL11_31") (pintype "bidirectional"))
    )
    (net (code "195") (name "unconnected-(U5-XTB-Pad4)") (class "Default")
      (node (ref "U5") (pin "4") (pinfunction "XTB_4") (pintype "bidirectional"))
    )
    (net (code "196") (name "unconnected-(U7-RFO-Pad24)") (class "Default")
      (node (ref "U7") (pin "24") (pinfunction "RFO_24") (pintype "bidirectional"))
    )
    (net (code "197") (name "unconnected-(U7-VR_PA-Pad1)") (class "Default")
      (node (ref "U7") (pin "1") (pinfunction "VR_PA_1") (pintype "bidirectional"))
    )
    (net (code "198") (name "unconnected-(U7-XTB-Pad4)") (class "Default")
      (node (ref "U7") (pin "4") (pinfunction "XTB_4") (pintype "bidirectional"))
    )
    (net (code "199") (name "unconnected-(U9-NC-Pad14)") (class "Default")
      (node (ref "U9") (pin "14") (pinfunction "NC_14") (pintype "bidirectional"))
    )
    (net (code "200") (name "unconnected-(U9-TX_ALT-Pad3)") (class "Default")
      (node (ref "U9") (pin "3") (pinfunction "TX_ALT_3") (pintype "bidirectional"))
    )
    (net (code "201") (name "unconnected-(U11-RFO-Pad23)") (class "Default")
      (node (ref "U11") (pin "23") (pinfunction "RFO_23") (pintype "bidirectional"))
    )
    (net (code "202") (name "unconnected-(U11-VR_PA-Pad24)") (class "Default")
      (node (ref "U11") (pin "24") (pinfunction "VR_PA_24") (pintype "bidirectional"))
    )
    (net (code "203") (name "unconnected-(U11-XTB-Pad4)") (class "Default")
      (node (ref "U11") (pin "4") (pinfunction "XTB_4") (pintype "bidirectional"))
    )
  )
)
